# oscilostor.net
KiCad netlist of a schematic drawn in Altium Designer
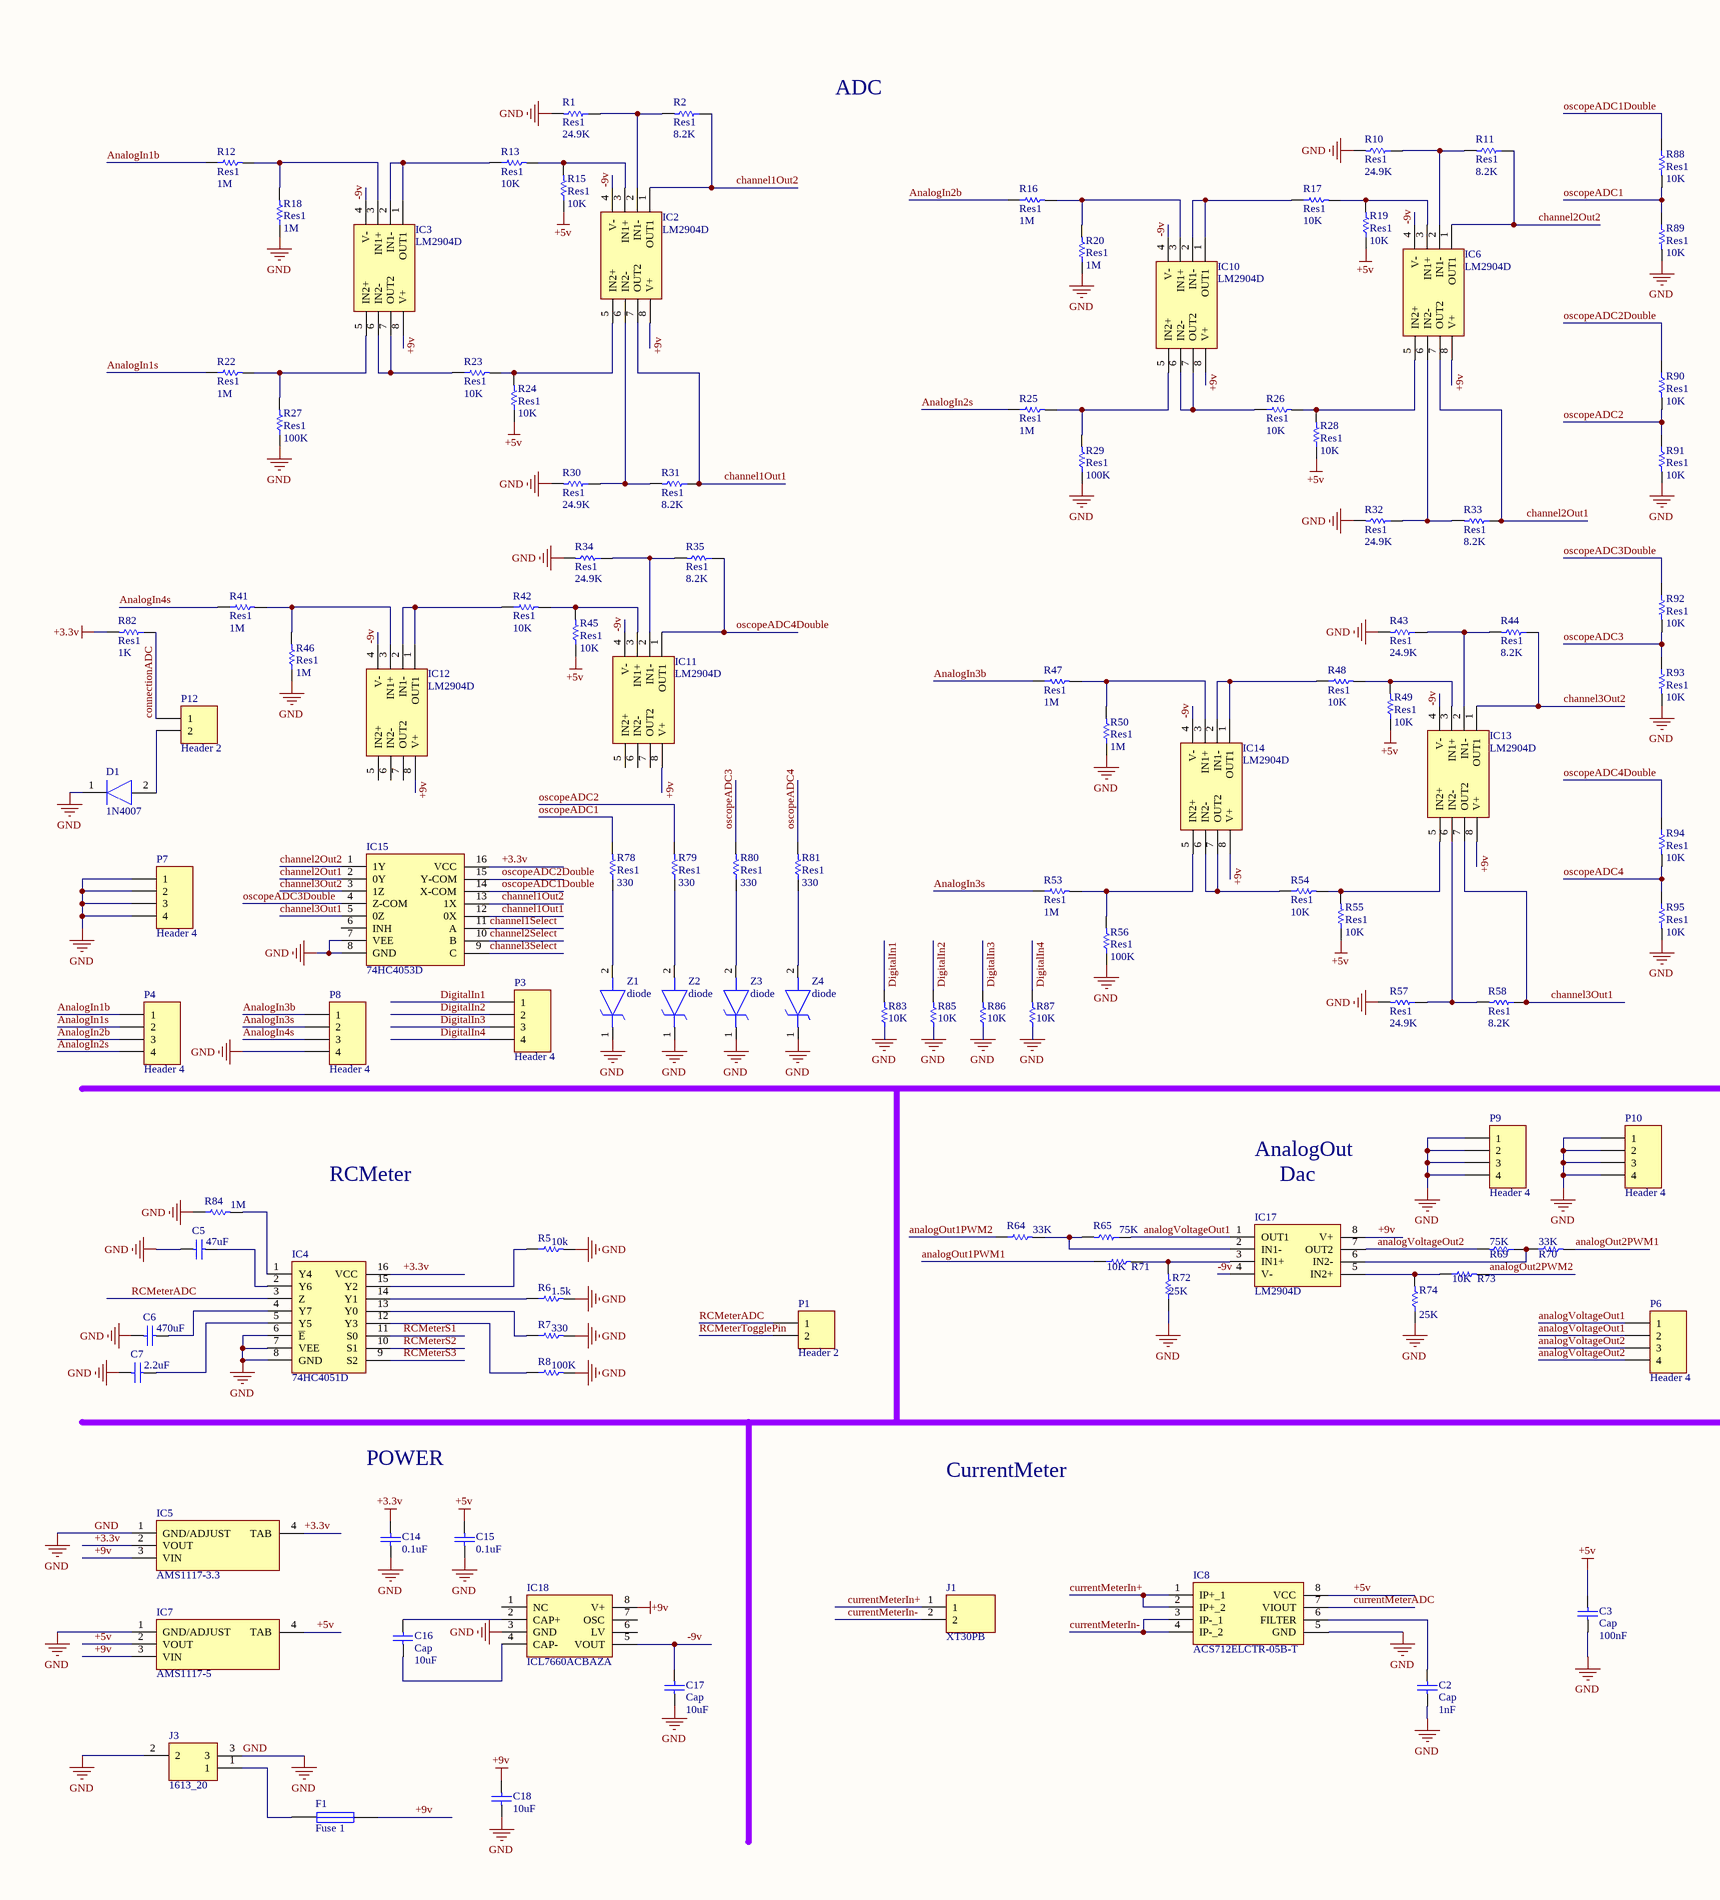
[diagram p0: oscilostor.SchDoc, left]
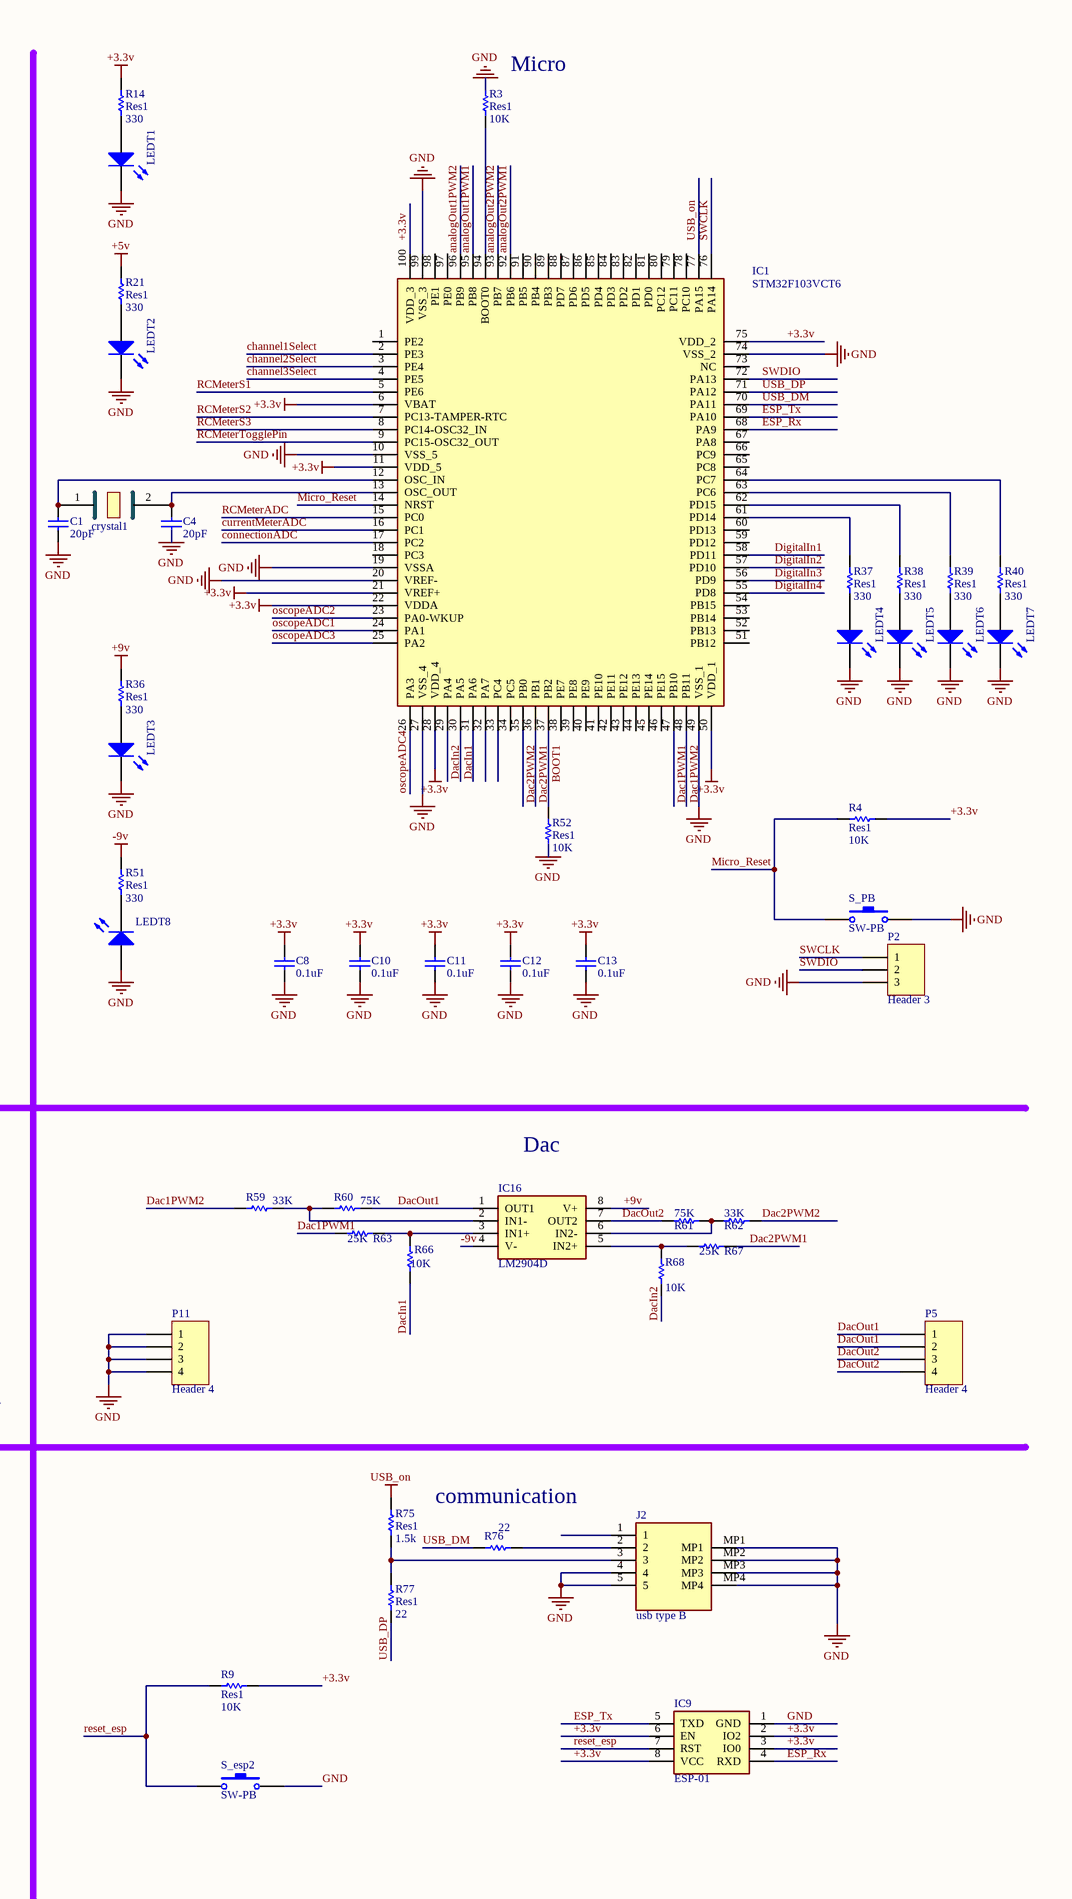
[diagram p1: oscilostor.SchDoc, right]

(export (version "E")
  (design (tool "Eeschema 10.0.6"))
  (components
    (comp (ref "C1")
      (value "20pF")
      (footprint "J1-0603")
      (description "Ceramic Chip Capacitor - Standard")
      (fields (field (name "Comment") "C0603") (field (name "PUBLISHER") "Altium Limited"))
      (libsource (lib "KEMET Chip Capacitor") (part "C0603"))
    )
    (comp (ref "C2")
      (value "Cap")
      (footprint "J1-0603")
      (description "Capacitor")
      (fields (field (name "ALTIUM_VALUE") "1nF") (field (name "PUBLISHER") "Altium Limited"))
      (libsource (lib "Miscellaneous Devices") (part "Cap"))
    )
    (comp (ref "C3")
      (value "Cap")
      (footprint "J1-0603")
      (description "Capacitor")
      (fields (field (name "ALTIUM_VALUE") "100nF") (field (name "PUBLISHER") "Altium Limited"))
      (libsource (lib "Miscellaneous Devices") (part "Cap"))
    )
    (comp (ref "C4")
      (value "20pF")
      (footprint "J1-0603")
      (description "Ceramic Chip Capacitor - Standard")
      (fields (field (name "Comment") "C0603") (field (name "PUBLISHER") "Altium Limited"))
      (libsource (lib "KEMET Chip Capacitor") (part "C0603"))
    )
    (comp (ref "C5")
      (value "47uF")
      (footprint "Deep Cap gerdaloo")
      (description "Capacitor")
      (fields (field (name "Comment") "Cap") (field (name "PUBLISHER") "Altium Limited"))
      (libsource (lib "Miscellaneous Devices") (part "Cap"))
    )
    (comp (ref "C6")
      (value "470uF")
      (footprint "Deep Cap gerdaloo")
      (description "Capacitor")
      (fields (field (name "Comment") "Cap") (field (name "PUBLISHER") "Altium Limited"))
      (libsource (lib "Miscellaneous Devices") (part "Cap"))
    )
    (comp (ref "C7")
      (value "2.2uF")
      (footprint "Deep Cap gerdaloo")
      (description "Capacitor")
      (fields (field (name "Comment") "Cap") (field (name "PUBLISHER") "Altium Limited"))
      (libsource (lib "Miscellaneous Devices") (part "Cap"))
    )
    (comp (ref "C8")
      (value "0.1uF")
      (footprint "J1-0603")
      (description "Ceramic Chip Capacitor - Standard")
      (fields (field (name "Comment") "C0603") (field (name "PUBLISHER") "Altium Limited"))
      (libsource (lib "KEMET Chip Capacitor") (part "C0603"))
    )
    (comp (ref "C10")
      (value "0.1uF")
      (footprint "J1-0603")
      (description "Ceramic Chip Capacitor - Standard")
      (fields (field (name "Comment") "C0603") (field (name "PUBLISHER") "Altium Limited"))
      (libsource (lib "KEMET Chip Capacitor") (part "C0603"))
    )
    (comp (ref "C11")
      (value "0.1uF")
      (footprint "J1-0603")
      (description "Ceramic Chip Capacitor - Standard")
      (fields (field (name "Comment") "C0603") (field (name "PUBLISHER") "Altium Limited"))
      (libsource (lib "KEMET Chip Capacitor") (part "C0603"))
    )
    (comp (ref "C12")
      (value "0.1uF")
      (footprint "J1-0603")
      (description "Ceramic Chip Capacitor - Standard")
      (fields (field (name "Comment") "C0603") (field (name "PUBLISHER") "Altium Limited"))
      (libsource (lib "KEMET Chip Capacitor") (part "C0603"))
    )
    (comp (ref "C13")
      (value "0.1uF")
      (footprint "J1-0603")
      (description "Ceramic Chip Capacitor - Standard")
      (fields (field (name "Comment") "C0603") (field (name "PUBLISHER") "Altium Limited"))
      (libsource (lib "KEMET Chip Capacitor") (part "C0603"))
    )
    (comp (ref "C14")
      (value "0.1uF")
      (footprint "J1-0603")
      (description "Ceramic Chip Capacitor - Standard")
      (fields (field (name "Comment") "C0603") (field (name "PUBLISHER") "Altium Limited"))
      (libsource (lib "KEMET Chip Capacitor") (part "C0603"))
    )
    (comp (ref "C15")
      (value "0.1uF")
      (footprint "J1-0603")
      (description "Ceramic Chip Capacitor - Standard")
      (fields (field (name "Comment") "C0603") (field (name "PUBLISHER") "Altium Limited"))
      (libsource (lib "KEMET Chip Capacitor") (part "C0603"))
    )
    (comp (ref "C16")
      (value "Cap")
      (footprint "J1-0603")
      (description "Capacitor")
      (fields (field (name "ALTIUM_VALUE") "10uF") (field (name "PUBLISHER") "Altium Limited"))
      (libsource (lib "Miscellaneous Devices") (part "Cap"))
    )
    (comp (ref "C17")
      (value "Cap")
      (footprint "J1-0603")
      (description "Capacitor")
      (fields (field (name "ALTIUM_VALUE") "10uF") (field (name "PUBLISHER") "Altium Limited"))
      (libsource (lib "Miscellaneous Devices") (part "Cap"))
    )
    (comp (ref "C18")
      (value "10uF")
      (footprint "J1-0603")
      (description "Ceramic Chip Capacitor - Standard")
      (fields (field (name "Comment") "C0603") (field (name "PUBLISHER") "Altium Limited"))
      (libsource (lib "KEMET Chip Capacitor") (part "C0603"))
    )
    (comp (ref "crystal1")
      (value "clockProducerDeep")
      (footprint "smd CRYSTAL")
      (libsource (lib "Schlib1") (part "deep crystal"))
    )
    (comp (ref "D1")
      (value "1N4007")
      (footprint "SamacSys:DIOM5327X242N")
      (description "Diode")
      (libsource (lib "*") (part "1N4007"))
    )
    (comp (ref "F1")
      (value "Fuse 1")
      (footprint "0805")
      (description "Fuse")
      (fields (field (name "PUBLISHER") "Altium Limited"))
      (libsource (lib "Miscellaneous Devices") (part "Fuse 1"))
    )
    (comp (ref "IC1")
      (value "STM32F103VCT6")
      (footprint "SamacSys:QFP50P1600X1600X160-100N")
      (description "Integrated Circuit")
      (fields (field (name "MOUSER PART NUMBER") "511-STM32F103VCT6"))
      (libsource (lib "*") (part "STM32F103VCT6"))
    )
    (comp (ref "IC2")
      (value "LM2904D")
      (footprint "SamacSys:SOIC127P600X175-8N")
      (description "Integrated Circuit")
      (fields (field (name "MOUSER PART NUMBER") "595-LM2904D"))
      (libsource (lib "*") (part "LM2904D"))
    )
    (comp (ref "IC3")
      (value "LM2904D")
      (footprint "SamacSys:SOIC127P600X175-8N")
      (description "Integrated Circuit")
      (fields (field (name "MOUSER PART NUMBER") "595-LM2904D"))
      (libsource (lib "*") (part "LM2904D"))
    )
    (comp (ref "IC4")
      (value "74HC4051D")
      (footprint "SamacSys:SOIC127P600X175-16N")
      (description "Integrated Circuit")
      (libsource (lib "*") (part "74HC4051D"))
    )
    (comp (ref "IC5")
      (value "AMS1117-3.3")
      (footprint "SamacSys:SOT229P700X180-4N")
      (description "Integrated Circuit")
      (fields (field (name "MANUFACTURER_PART_NUMBER") "AMS1117-1.5"))
      (libsource (lib "*") (part "AMS1117-1.5"))
    )
    (comp (ref "IC6")
      (value "LM2904D")
      (footprint "SamacSys:SOIC127P600X175-8N")
      (description "Integrated Circuit")
      (fields (field (name "MOUSER PART NUMBER") "595-LM2904D"))
      (libsource (lib "*") (part "LM2904D"))
    )
    (comp (ref "IC7")
      (value "AMS1117-5")
      (footprint "SamacSys:SOT229P700X180-4N")
      (description "Integrated Circuit")
      (fields (field (name "MANUFACTURER_PART_NUMBER") "AMS1117-1.5"))
      (libsource (lib "*") (part "AMS1117-1.5"))
    )
    (comp (ref "IC8")
      (value "ACS712ELCTR-05B-T")
      (footprint "SamacSys:SOIC127P600X175-8N")
      (description "Integrated Circuit")
      (libsource (lib "*") (part "ACS712ELCTR-05B-T"))
    )
    (comp (ref "IC9")
      (value "ESP-01")
      (footprint "HDR2X4")
      (description "Integrated Circuit")
      (libsource (lib "*") (part "ESP-01"))
    )
    (comp (ref "IC10")
      (value "LM2904D")
      (footprint "SamacSys:SOIC127P600X175-8N")
      (description "Integrated Circuit")
      (fields (field (name "MOUSER PART NUMBER") "595-LM2904D"))
      (libsource (lib "*") (part "LM2904D"))
    )
    (comp (ref "IC11")
      (value "LM2904D")
      (footprint "SamacSys:SOIC127P600X175-8N")
      (description "Integrated Circuit")
      (fields (field (name "MOUSER PART NUMBER") "595-LM2904D"))
      (libsource (lib "*") (part "LM2904D"))
    )
    (comp (ref "IC12")
      (value "LM2904D")
      (footprint "SamacSys:SOIC127P600X175-8N")
      (description "Integrated Circuit")
      (fields (field (name "MOUSER PART NUMBER") "595-LM2904D"))
      (libsource (lib "*") (part "LM2904D"))
    )
    (comp (ref "IC13")
      (value "LM2904D")
      (footprint "SamacSys:SOIC127P600X175-8N")
      (description "Integrated Circuit")
      (fields (field (name "MOUSER PART NUMBER") "595-LM2904D"))
      (libsource (lib "*") (part "LM2904D"))
    )
    (comp (ref "IC14")
      (value "LM2904D")
      (footprint "SamacSys:SOIC127P600X175-8N")
      (description "Integrated Circuit")
      (fields (field (name "MOUSER PART NUMBER") "595-LM2904D"))
      (libsource (lib "*") (part "LM2904D"))
    )
    (comp (ref "IC15")
      (value "74HC4053D")
      (footprint "SamacSys:SOIC127P600X175-16N")
      (description "Integrated Circuit")
      (fields (field (name "MOUSER PART NUMBER") "757-74HC4053D"))
      (libsource (lib "*") (part "74HC4053D"))
    )
    (comp (ref "IC16")
      (value "LM2904D")
      (footprint "SamacSys:SOIC127P600X175-8N")
      (description "Integrated Circuit")
      (fields (field (name "MOUSER PART NUMBER") "595-LM2904D"))
      (libsource (lib "") (part "LM2904D_1"))
    )
    (comp (ref "IC17")
      (value "LM2904D")
      (footprint "SamacSys:SOIC127P600X175-8N")
      (description "Integrated Circuit")
      (fields (field (name "MOUSER PART NUMBER") "595-LM2904D"))
      (libsource (lib "") (part "LM2904D_1"))
    )
    (comp (ref "IC18")
      (value "ICL7660ACBAZA")
      (footprint "SamacSys:SOIC127P600X175-8N")
      (description "Integrated Circuit")
      (fields (field (name "MOUSER PART NUMBER") "968-ICL7660ACBAZA"))
      (libsource (lib "*") (part "ICL7660ACBAZA"))
    )
    (comp (ref "J1")
      (value "XT30PB")
      (footprint "SamacSys:XT30PB")
      (description "Connector")
      (libsource (lib "*") (part "XT30PB"))
    )
    (comp (ref "J2")
      (value "usb type B")
      (footprint "SamacSys:0474910001")
      (description "Connector")
      (fields (field (name "MANUFACTURER_PART_NUMBER") "0474910001"))
      (libsource (lib "SamacSys") (part "0474910001"))
    )
    (comp (ref "J3")
      (value "1613_20")
      (footprint "SamacSys:161320")
      (description "Connector")
      (fields (field (name "MANUFACTURER_PART_NUMBER") "1613 20"))
      (libsource (lib "*") (part "1613_20"))
    )
    (comp (ref "LEDT1")
      (value "~")
      (footprint "3518")
      (description "Typical BLUE SiC LED")
      (fields (field (name "PUBLISHER") "Altium Limited"))
      (libsource (lib "Miscellaneous Devices") (part "LED3"))
    )
    (comp (ref "LEDT2")
      (value "~")
      (footprint "3518")
      (description "Typical BLUE SiC LED")
      (fields (field (name "PUBLISHER") "Altium Limited"))
      (libsource (lib "Miscellaneous Devices") (part "LED3"))
    )
    (comp (ref "LEDT3")
      (value "~")
      (footprint "3518")
      (description "Typical BLUE SiC LED")
      (fields (field (name "PUBLISHER") "Altium Limited"))
      (libsource (lib "Miscellaneous Devices") (part "LED3"))
    )
    (comp (ref "LEDT4")
      (value "~")
      (footprint "3518")
      (description "Typical BLUE SiC LED")
      (fields (field (name "PUBLISHER") "Altium Limited"))
      (libsource (lib "Miscellaneous Devices") (part "LED3"))
    )
    (comp (ref "LEDT5")
      (value "~")
      (footprint "3518")
      (description "Typical BLUE SiC LED")
      (fields (field (name "PUBLISHER") "Altium Limited"))
      (libsource (lib "Miscellaneous Devices") (part "LED3"))
    )
    (comp (ref "LEDT6")
      (value "~")
      (footprint "3518")
      (description "Typical BLUE SiC LED")
      (fields (field (name "PUBLISHER") "Altium Limited"))
      (libsource (lib "Miscellaneous Devices") (part "LED3"))
    )
    (comp (ref "LEDT7")
      (value "~")
      (footprint "3518")
      (description "Typical BLUE SiC LED")
      (fields (field (name "PUBLISHER") "Altium Limited"))
      (libsource (lib "Miscellaneous Devices") (part "LED3"))
    )
    (comp (ref "LEDT8")
      (value "~")
      (footprint "3518")
      (description "Typical BLUE SiC LED")
      (fields (field (name "PUBLISHER") "Altium Limited"))
      (libsource (lib "Miscellaneous Devices") (part "LED3"))
    )
    (comp (ref "P1")
      (value "Header 2")
      (footprint "HDR1X2")
      (description "Header, 2-Pin")
      (fields (field (name "PUBLISHER") "Altium Limited"))
      (libsource (lib "Miscellaneous Connectors") (part "Header 2"))
    )
    (comp (ref "P2")
      (value "Header 3")
      (footprint "HDR1X3")
      (description "Header, 3-Pin")
      (fields (field (name "PUBLISHER") "Altium Limited"))
      (libsource (lib "Miscellaneous Connectors") (part "Header 3"))
    )
    (comp (ref "P3")
      (value "Header 4")
      (footprint "HDR1X4")
      (description "Header, 4-Pin")
      (fields (field (name "PUBLISHER") "Altium Limited"))
      (libsource (lib "Miscellaneous Connectors") (part "Header 4"))
    )
    (comp (ref "P4")
      (value "Header 4")
      (footprint "HDR1X4")
      (description "Header, 4-Pin")
      (fields (field (name "PUBLISHER") "Altium Limited"))
      (libsource (lib "Miscellaneous Connectors") (part "Header 4"))
    )
    (comp (ref "P5")
      (value "Header 4")
      (footprint "HDR1X4")
      (description "Header, 4-Pin")
      (fields (field (name "PUBLISHER") "Altium Limited"))
      (libsource (lib "Miscellaneous Connectors") (part "Header 4"))
    )
    (comp (ref "P6")
      (value "Header 4")
      (footprint "HDR1X4")
      (description "Header, 4-Pin")
      (fields (field (name "PUBLISHER") "Altium Limited"))
      (libsource (lib "Miscellaneous Connectors") (part "Header 4"))
    )
    (comp (ref "P7")
      (value "Header 4")
      (footprint "HDR1X4")
      (description "Header, 4-Pin")
      (fields (field (name "PUBLISHER") "Altium Limited"))
      (libsource (lib "Miscellaneous Connectors") (part "Header 4"))
    )
    (comp (ref "P8")
      (value "Header 4")
      (footprint "HDR1X4")
      (description "Header, 4-Pin")
      (fields (field (name "PUBLISHER") "Altium Limited"))
      (libsource (lib "Miscellaneous Connectors") (part "Header 4"))
    )
    (comp (ref "P9")
      (value "Header 4")
      (footprint "HDR1X4")
      (description "Header, 4-Pin")
      (fields (field (name "PUBLISHER") "Altium Limited"))
      (libsource (lib "Miscellaneous Connectors") (part "Header 4"))
    )
    (comp (ref "P10")
      (value "Header 4")
      (footprint "HDR1X4")
      (description "Header, 4-Pin")
      (fields (field (name "PUBLISHER") "Altium Limited"))
      (libsource (lib "Miscellaneous Connectors") (part "Header 4"))
    )
    (comp (ref "P11")
      (value "Header 4")
      (footprint "HDR1X4")
      (description "Header, 4-Pin")
      (fields (field (name "PUBLISHER") "Altium Limited"))
      (libsource (lib "Miscellaneous Connectors") (part "Header 4"))
    )
    (comp (ref "P12")
      (value "Header 2")
      (footprint "HDR1X2")
      (description "Header, 2-Pin")
      (fields (field (name "PUBLISHER") "Altium Limited"))
      (libsource (lib "Miscellaneous Connectors") (part "Header 2"))
    )
    (comp (ref "R1")
      (value "Res1")
      (footprint "J1-0603")
      (description "Resistor")
      (fields (field (name "ALTIUM_VALUE") "24.9K") (field (name "PUBLISHER") "Altium Limited"))
      (libsource (lib "Miscellaneous Devices") (part "Res1"))
    )
    (comp (ref "R2")
      (value "Res1")
      (footprint "J1-0603")
      (description "Resistor")
      (fields (field (name "ALTIUM_VALUE") "8.2K") (field (name "PUBLISHER") "Altium Limited"))
      (libsource (lib "Miscellaneous Devices") (part "Res1"))
    )
    (comp (ref "R3")
      (value "Res1")
      (footprint "J1-0603")
      (description "Resistor")
      (fields (field (name "ALTIUM_VALUE") "10K") (field (name "PUBLISHER") "Altium Limited"))
      (libsource (lib "Miscellaneous Devices") (part "Res1"))
    )
    (comp (ref "R4")
      (value "Res1")
      (footprint "J1-0603")
      (description "Resistor")
      (fields (field (name "ALTIUM_VALUE") "10K") (field (name "PUBLISHER") "Altium Limited"))
      (libsource (lib "Miscellaneous Devices") (part "Res1"))
    )
    (comp (ref "R5")
      (value "10k")
      (footprint "J1-0603")
      (description "Resistor")
      (fields (field (name "Comment") "Res1") (field (name "PUBLISHER") "Altium Limited"))
      (libsource (lib "Miscellaneous Devices") (part "Res1"))
    )
    (comp (ref "R6")
      (value "1.5k")
      (footprint "J1-0603")
      (description "Resistor")
      (fields (field (name "Comment") "Res1") (field (name "PUBLISHER") "Altium Limited"))
      (libsource (lib "Miscellaneous Devices") (part "Res1"))
    )
    (comp (ref "R7")
      (value "330")
      (footprint "J1-0603")
      (description "Resistor")
      (fields (field (name "Comment") "Res1") (field (name "PUBLISHER") "Altium Limited"))
      (libsource (lib "Miscellaneous Devices") (part "Res1"))
    )
    (comp (ref "R8")
      (value "100K")
      (footprint "J1-0603")
      (description "Resistor")
      (fields (field (name "Comment") "Res1") (field (name "PUBLISHER") "Altium Limited"))
      (libsource (lib "Miscellaneous Devices") (part "Res1"))
    )
    (comp (ref "R9")
      (value "Res1")
      (footprint "J1-0603")
      (description "Resistor")
      (fields (field (name "ALTIUM_VALUE") "10K") (field (name "PUBLISHER") "Altium Limited"))
      (libsource (lib "Miscellaneous Devices") (part "Res1"))
    )
    (comp (ref "R10")
      (value "Res1")
      (footprint "J1-0603")
      (description "Resistor")
      (fields (field (name "ALTIUM_VALUE") "24.9K") (field (name "PUBLISHER") "Altium Limited"))
      (libsource (lib "Miscellaneous Devices") (part "Res1"))
    )
    (comp (ref "R11")
      (value "Res1")
      (footprint "J1-0603")
      (description "Resistor")
      (fields (field (name "ALTIUM_VALUE") "8.2K") (field (name "PUBLISHER") "Altium Limited"))
      (libsource (lib "Miscellaneous Devices") (part "Res1"))
    )
    (comp (ref "R12")
      (value "Res1")
      (footprint "J1-0603")
      (description "Resistor")
      (fields (field (name "ALTIUM_VALUE") "1M") (field (name "PUBLISHER") "Altium Limited"))
      (libsource (lib "Miscellaneous Devices") (part "Res1"))
    )
    (comp (ref "R13")
      (value "Res1")
      (footprint "J1-0603")
      (description "Resistor")
      (fields (field (name "ALTIUM_VALUE") "10K") (field (name "PUBLISHER") "Altium Limited"))
      (libsource (lib "Miscellaneous Devices") (part "Res1"))
    )
    (comp (ref "R14")
      (value "Res1")
      (footprint "j1-0603")
      (description "Resistor")
      (fields (field (name "ALTIUM_VALUE") "330") (field (name "PUBLISHER") "Altium Limited"))
      (libsource (lib "Miscellaneous Devices") (part "Res1"))
    )
    (comp (ref "R15")
      (value "Res1")
      (footprint "J1-0603")
      (description "Resistor")
      (fields (field (name "ALTIUM_VALUE") "10K") (field (name "PUBLISHER") "Altium Limited"))
      (libsource (lib "Miscellaneous Devices") (part "Res1"))
    )
    (comp (ref "R16")
      (value "Res1")
      (footprint "J1-0603")
      (description "Resistor")
      (fields (field (name "ALTIUM_VALUE") "1M") (field (name "PUBLISHER") "Altium Limited"))
      (libsource (lib "Miscellaneous Devices") (part "Res1"))
    )
    (comp (ref "R17")
      (value "Res1")
      (footprint "J1-0603")
      (description "Resistor")
      (fields (field (name "ALTIUM_VALUE") "10K") (field (name "PUBLISHER") "Altium Limited"))
      (libsource (lib "Miscellaneous Devices") (part "Res1"))
    )
    (comp (ref "R18")
      (value "Res1")
      (footprint "J1-0603")
      (description "Resistor")
      (fields (field (name "ALTIUM_VALUE") "1M") (field (name "PUBLISHER") "Altium Limited"))
      (libsource (lib "Miscellaneous Devices") (part "Res1"))
    )
    (comp (ref "R19")
      (value "Res1")
      (footprint "J1-0603")
      (description "Resistor")
      (fields (field (name "ALTIUM_VALUE") "10K") (field (name "PUBLISHER") "Altium Limited"))
      (libsource (lib "Miscellaneous Devices") (part "Res1"))
    )
    (comp (ref "R20")
      (value "Res1")
      (footprint "J1-0603")
      (description "Resistor")
      (fields (field (name "ALTIUM_VALUE") "1M") (field (name "PUBLISHER") "Altium Limited"))
      (libsource (lib "Miscellaneous Devices") (part "Res1"))
    )
    (comp (ref "R21")
      (value "Res1")
      (footprint "j1-0603")
      (description "Resistor")
      (fields (field (name "ALTIUM_VALUE") "330") (field (name "PUBLISHER") "Altium Limited"))
      (libsource (lib "Miscellaneous Devices") (part "Res1"))
    )
    (comp (ref "R22")
      (value "Res1")
      (footprint "J1-0603")
      (description "Resistor")
      (fields (field (name "ALTIUM_VALUE") "1M") (field (name "PUBLISHER") "Altium Limited"))
      (libsource (lib "Miscellaneous Devices") (part "Res1"))
    )
    (comp (ref "R23")
      (value "Res1")
      (footprint "J1-0603")
      (description "Resistor")
      (fields (field (name "ALTIUM_VALUE") "10K") (field (name "PUBLISHER") "Altium Limited"))
      (libsource (lib "Miscellaneous Devices") (part "Res1"))
    )
    (comp (ref "R24")
      (value "Res1")
      (footprint "J1-0603")
      (description "Resistor")
      (fields (field (name "ALTIUM_VALUE") "10K") (field (name "PUBLISHER") "Altium Limited"))
      (libsource (lib "Miscellaneous Devices") (part "Res1"))
    )
    (comp (ref "R25")
      (value "Res1")
      (footprint "J1-0603")
      (description "Resistor")
      (fields (field (name "ALTIUM_VALUE") "1M") (field (name "PUBLISHER") "Altium Limited"))
      (libsource (lib "Miscellaneous Devices") (part "Res1"))
    )
    (comp (ref "R26")
      (value "Res1")
      (footprint "J1-0603")
      (description "Resistor")
      (fields (field (name "ALTIUM_VALUE") "10K") (field (name "PUBLISHER") "Altium Limited"))
      (libsource (lib "Miscellaneous Devices") (part "Res1"))
    )
    (comp (ref "R27")
      (value "Res1")
      (footprint "J1-0603")
      (description "Resistor")
      (fields (field (name "ALTIUM_VALUE") "100K") (field (name "PUBLISHER") "Altium Limited"))
      (libsource (lib "Miscellaneous Devices") (part "Res1"))
    )
    (comp (ref "R28")
      (value "Res1")
      (footprint "J1-0603")
      (description "Resistor")
      (fields (field (name "ALTIUM_VALUE") "10K") (field (name "PUBLISHER") "Altium Limited"))
      (libsource (lib "Miscellaneous Devices") (part "Res1"))
    )
    (comp (ref "R29")
      (value "Res1")
      (footprint "J1-0603")
      (description "Resistor")
      (fields (field (name "ALTIUM_VALUE") "100K") (field (name "PUBLISHER") "Altium Limited"))
      (libsource (lib "Miscellaneous Devices") (part "Res1"))
    )
    (comp (ref "R30")
      (value "Res1")
      (footprint "J1-0603")
      (description "Resistor")
      (fields (field (name "ALTIUM_VALUE") "24.9K") (field (name "PUBLISHER") "Altium Limited"))
      (libsource (lib "Miscellaneous Devices") (part "Res1"))
    )
    (comp (ref "R31")
      (value "Res1")
      (footprint "J1-0603")
      (description "Resistor")
      (fields (field (name "ALTIUM_VALUE") "8.2K") (field (name "PUBLISHER") "Altium Limited"))
      (libsource (lib "Miscellaneous Devices") (part "Res1"))
    )
    (comp (ref "R32")
      (value "Res1")
      (footprint "J1-0603")
      (description "Resistor")
      (fields (field (name "ALTIUM_VALUE") "24.9K") (field (name "PUBLISHER") "Altium Limited"))
      (libsource (lib "Miscellaneous Devices") (part "Res1"))
    )
    (comp (ref "R33")
      (value "Res1")
      (footprint "J1-0603")
      (description "Resistor")
      (fields (field (name "ALTIUM_VALUE") "8.2K") (field (name "PUBLISHER") "Altium Limited"))
      (libsource (lib "Miscellaneous Devices") (part "Res1"))
    )
    (comp (ref "R34")
      (value "Res1")
      (footprint "J1-0603")
      (description "Resistor")
      (fields (field (name "ALTIUM_VALUE") "24.9K") (field (name "PUBLISHER") "Altium Limited"))
      (libsource (lib "Miscellaneous Devices") (part "Res1"))
    )
    (comp (ref "R35")
      (value "Res1")
      (footprint "J1-0603")
      (description "Resistor")
      (fields (field (name "ALTIUM_VALUE") "8.2K") (field (name "PUBLISHER") "Altium Limited"))
      (libsource (lib "Miscellaneous Devices") (part "Res1"))
    )
    (comp (ref "R36")
      (value "Res1")
      (footprint "j1-0603")
      (description "Resistor")
      (fields (field (name "ALTIUM_VALUE") "330") (field (name "PUBLISHER") "Altium Limited"))
      (libsource (lib "Miscellaneous Devices") (part "Res1"))
    )
    (comp (ref "R37")
      (value "Res1")
      (footprint "j1-0603")
      (description "Resistor")
      (fields (field (name "ALTIUM_VALUE") "330") (field (name "PUBLISHER") "Altium Limited"))
      (libsource (lib "Miscellaneous Devices") (part "Res1"))
    )
    (comp (ref "R38")
      (value "Res1")
      (footprint "j1-0603")
      (description "Resistor")
      (fields (field (name "ALTIUM_VALUE") "330") (field (name "PUBLISHER") "Altium Limited"))
      (libsource (lib "Miscellaneous Devices") (part "Res1"))
    )
    (comp (ref "R39")
      (value "Res1")
      (footprint "j1-0603")
      (description "Resistor")
      (fields (field (name "ALTIUM_VALUE") "330") (field (name "PUBLISHER") "Altium Limited"))
      (libsource (lib "Miscellaneous Devices") (part "Res1"))
    )
    (comp (ref "R40")
      (value "Res1")
      (footprint "j1-0603")
      (description "Resistor")
      (fields (field (name "ALTIUM_VALUE") "330") (field (name "PUBLISHER") "Altium Limited"))
      (libsource (lib "Miscellaneous Devices") (part "Res1"))
    )
    (comp (ref "R41")
      (value "Res1")
      (footprint "J1-0603")
      (description "Resistor")
      (fields (field (name "ALTIUM_VALUE") "1M") (field (name "PUBLISHER") "Altium Limited"))
      (libsource (lib "Miscellaneous Devices") (part "Res1"))
    )
    (comp (ref "R42")
      (value "Res1")
      (footprint "J1-0603")
      (description "Resistor")
      (fields (field (name "ALTIUM_VALUE") "10K") (field (name "PUBLISHER") "Altium Limited"))
      (libsource (lib "Miscellaneous Devices") (part "Res1"))
    )
    (comp (ref "R43")
      (value "Res1")
      (footprint "J1-0603")
      (description "Resistor")
      (fields (field (name "ALTIUM_VALUE") "24.9K") (field (name "PUBLISHER") "Altium Limited"))
      (libsource (lib "Miscellaneous Devices") (part "Res1"))
    )
    (comp (ref "R44")
      (value "Res1")
      (footprint "J1-0603")
      (description "Resistor")
      (fields (field (name "ALTIUM_VALUE") "8.2K") (field (name "PUBLISHER") "Altium Limited"))
      (libsource (lib "Miscellaneous Devices") (part "Res1"))
    )
    (comp (ref "R45")
      (value "Res1")
      (footprint "J1-0603")
      (description "Resistor")
      (fields (field (name "ALTIUM_VALUE") "10K") (field (name "PUBLISHER") "Altium Limited"))
      (libsource (lib "Miscellaneous Devices") (part "Res1"))
    )
    (comp (ref "R46")
      (value "Res1")
      (footprint "J1-0603")
      (description "Resistor")
      (fields (field (name "ALTIUM_VALUE") "1M") (field (name "PUBLISHER") "Altium Limited"))
      (libsource (lib "Miscellaneous Devices") (part "Res1"))
    )
    (comp (ref "R47")
      (value "Res1")
      (footprint "J1-0603")
      (description "Resistor")
      (fields (field (name "ALTIUM_VALUE") "1M") (field (name "PUBLISHER") "Altium Limited"))
      (libsource (lib "Miscellaneous Devices") (part "Res1"))
    )
    (comp (ref "R48")
      (value "Res1")
      (footprint "J1-0603")
      (description "Resistor")
      (fields (field (name "ALTIUM_VALUE") "10K") (field (name "PUBLISHER") "Altium Limited"))
      (libsource (lib "Miscellaneous Devices") (part "Res1"))
    )
    (comp (ref "R49")
      (value "Res1")
      (footprint "J1-0603")
      (description "Resistor")
      (fields (field (name "ALTIUM_VALUE") "10K") (field (name "PUBLISHER") "Altium Limited"))
      (libsource (lib "Miscellaneous Devices") (part "Res1"))
    )
    (comp (ref "R50")
      (value "Res1")
      (footprint "J1-0603")
      (description "Resistor")
      (fields (field (name "ALTIUM_VALUE") "1M") (field (name "PUBLISHER") "Altium Limited"))
      (libsource (lib "Miscellaneous Devices") (part "Res1"))
    )
    (comp (ref "R51")
      (value "Res1")
      (footprint "j1-0603")
      (description "Resistor")
      (fields (field (name "ALTIUM_VALUE") "330") (field (name "PUBLISHER") "Altium Limited"))
      (libsource (lib "Miscellaneous Devices") (part "Res1"))
    )
    (comp (ref "R52")
      (value "Res1")
      (footprint "J1-0603")
      (description "Resistor")
      (fields (field (name "ALTIUM_VALUE") "10K") (field (name "PUBLISHER") "Altium Limited"))
      (libsource (lib "Miscellaneous Devices") (part "Res1"))
    )
    (comp (ref "R53")
      (value "Res1")
      (footprint "J1-0603")
      (description "Resistor")
      (fields (field (name "ALTIUM_VALUE") "1M") (field (name "PUBLISHER") "Altium Limited"))
      (libsource (lib "Miscellaneous Devices") (part "Res1"))
    )
    (comp (ref "R54")
      (value "Res1")
      (footprint "J1-0603")
      (description "Resistor")
      (fields (field (name "ALTIUM_VALUE") "10K") (field (name "PUBLISHER") "Altium Limited"))
      (libsource (lib "Miscellaneous Devices") (part "Res1"))
    )
    (comp (ref "R55")
      (value "Res1")
      (footprint "J1-0603")
      (description "Resistor")
      (fields (field (name "ALTIUM_VALUE") "10K") (field (name "PUBLISHER") "Altium Limited"))
      (libsource (lib "Miscellaneous Devices") (part "Res1"))
    )
    (comp (ref "R56")
      (value "Res1")
      (footprint "J1-0603")
      (description "Resistor")
      (fields (field (name "ALTIUM_VALUE") "100K") (field (name "PUBLISHER") "Altium Limited"))
      (libsource (lib "Miscellaneous Devices") (part "Res1"))
    )
    (comp (ref "R57")
      (value "Res1")
      (footprint "J1-0603")
      (description "Resistor")
      (fields (field (name "ALTIUM_VALUE") "24.9K") (field (name "PUBLISHER") "Altium Limited"))
      (libsource (lib "Miscellaneous Devices") (part "Res1"))
    )
    (comp (ref "R58")
      (value "Res1")
      (footprint "J1-0603")
      (description "Resistor")
      (fields (field (name "ALTIUM_VALUE") "8.2K") (field (name "PUBLISHER") "Altium Limited"))
      (libsource (lib "Miscellaneous Devices") (part "Res1"))
    )
    (comp (ref "R59")
      (value "33K")
      (footprint "J1-0603")
      (description "Resistor")
      (fields (field (name "Comment") "Res1") (field (name "PUBLISHER") "Altium Limited"))
      (libsource (lib "Miscellaneous Devices") (part "Res1"))
    )
    (comp (ref "R60")
      (value "75K")
      (footprint "J1-0603")
      (description "Resistor")
      (fields (field (name "Comment") "Res1") (field (name "PUBLISHER") "Altium Limited"))
      (libsource (lib "Miscellaneous Devices") (part "Res1"))
    )
    (comp (ref "R61")
      (value "75K")
      (footprint "J1-0603")
      (description "Resistor")
      (fields (field (name "Comment") "Res1") (field (name "PUBLISHER") "Altium Limited"))
      (libsource (lib "Miscellaneous Devices") (part "Res1"))
    )
    (comp (ref "R62")
      (value "33K")
      (footprint "J1-0603")
      (description "Resistor")
      (fields (field (name "Comment") "Res1") (field (name "PUBLISHER") "Altium Limited"))
      (libsource (lib "Miscellaneous Devices") (part "Res1"))
    )
    (comp (ref "R63")
      (value "25K")
      (footprint "J1-0603")
      (description "Resistor")
      (fields (field (name "Comment") "Res1") (field (name "PUBLISHER") "Altium Limited"))
      (libsource (lib "Miscellaneous Devices") (part "Res1"))
    )
    (comp (ref "R64")
      (value "33K")
      (footprint "J1-0603")
      (description "Resistor")
      (fields (field (name "Comment") "Res1") (field (name "PUBLISHER") "Altium Limited"))
      (libsource (lib "Miscellaneous Devices") (part "Res1"))
    )
    (comp (ref "R65")
      (value "75K")
      (footprint "J1-0603")
      (description "Resistor")
      (fields (field (name "Comment") "Res1") (field (name "PUBLISHER") "Altium Limited"))
      (libsource (lib "Miscellaneous Devices") (part "Res1"))
    )
    (comp (ref "R66")
      (value "10K")
      (footprint "J1-0603")
      (description "Resistor")
      (fields (field (name "Comment") "Res1") (field (name "PUBLISHER") "Altium Limited"))
      (libsource (lib "Miscellaneous Devices") (part "Res1"))
    )
    (comp (ref "R67")
      (value "25K")
      (footprint "J1-0603")
      (description "Resistor")
      (fields (field (name "Comment") "Res1") (field (name "PUBLISHER") "Altium Limited"))
      (libsource (lib "Miscellaneous Devices") (part "Res1"))
    )
    (comp (ref "R68")
      (value "10K")
      (footprint "J1-0603")
      (description "Resistor")
      (fields (field (name "Comment") "Res1") (field (name "PUBLISHER") "Altium Limited"))
      (libsource (lib "Miscellaneous Devices") (part "Res1"))
    )
    (comp (ref "R69")
      (value "75K")
      (footprint "J1-0603")
      (description "Resistor")
      (fields (field (name "Comment") "Res1") (field (name "PUBLISHER") "Altium Limited"))
      (libsource (lib "Miscellaneous Devices") (part "Res1"))
    )
    (comp (ref "R70")
      (value "33K")
      (footprint "J1-0603")
      (description "Resistor")
      (fields (field (name "Comment") "Res1") (field (name "PUBLISHER") "Altium Limited"))
      (libsource (lib "Miscellaneous Devices") (part "Res1"))
    )
    (comp (ref "R71")
      (value "10K")
      (footprint "J1-0603")
      (description "Resistor")
      (fields (field (name "Comment") "Res1") (field (name "PUBLISHER") "Altium Limited"))
      (libsource (lib "Miscellaneous Devices") (part "Res1"))
    )
    (comp (ref "R72")
      (value "25K")
      (footprint "J1-0603")
      (description "Resistor")
      (fields (field (name "Comment") "Res1") (field (name "PUBLISHER") "Altium Limited"))
      (libsource (lib "Miscellaneous Devices") (part "Res1"))
    )
    (comp (ref "R73")
      (value "10K")
      (footprint "J1-0603")
      (description "Resistor")
      (fields (field (name "Comment") "Res1") (field (name "PUBLISHER") "Altium Limited"))
      (libsource (lib "Miscellaneous Devices") (part "Res1"))
    )
    (comp (ref "R74")
      (value "25K")
      (footprint "J1-0603")
      (description "Resistor")
      (fields (field (name "Comment") "Res1") (field (name "PUBLISHER") "Altium Limited"))
      (libsource (lib "Miscellaneous Devices") (part "Res1"))
    )
    (comp (ref "R75")
      (value "Res1")
      (footprint "J1-0603")
      (description "Resistor")
      (fields (field (name "ALTIUM_VALUE") "1.5k") (field (name "PUBLISHER") "Altium Limited"))
      (libsource (lib "Miscellaneous Devices") (part "Res1"))
    )
    (comp (ref "R76")
      (value "22")
      (footprint "J1-0603")
      (description "Resistor")
      (fields (field (name "Comment") "Res1") (field (name "PUBLISHER") "Altium Limited"))
      (libsource (lib "Miscellaneous Devices") (part "Res1"))
    )
    (comp (ref "R77")
      (value "Res1")
      (footprint "J1-0603")
      (description "Resistor")
      (fields (field (name "ALTIUM_VALUE") "22") (field (name "PUBLISHER") "Altium Limited"))
      (libsource (lib "Miscellaneous Devices") (part "Res1"))
    )
    (comp (ref "R78")
      (value "Res1")
      (footprint "J1-0603")
      (description "Resistor")
      (fields (field (name "ALTIUM_VALUE") "330") (field (name "PUBLISHER") "Altium Limited"))
      (libsource (lib "Miscellaneous Devices") (part "Res1"))
    )
    (comp (ref "R79")
      (value "Res1")
      (footprint "J1-0603")
      (description "Resistor")
      (fields (field (name "ALTIUM_VALUE") "330") (field (name "PUBLISHER") "Altium Limited"))
      (libsource (lib "Miscellaneous Devices") (part "Res1"))
    )
    (comp (ref "R80")
      (value "Res1")
      (footprint "J1-0603")
      (description "Resistor")
      (fields (field (name "ALTIUM_VALUE") "330") (field (name "PUBLISHER") "Altium Limited"))
      (libsource (lib "Miscellaneous Devices") (part "Res1"))
    )
    (comp (ref "R81")
      (value "Res1")
      (footprint "J1-0603")
      (description "Resistor")
      (fields (field (name "ALTIUM_VALUE") "330") (field (name "PUBLISHER") "Altium Limited"))
      (libsource (lib "Miscellaneous Devices") (part "Res1"))
    )
    (comp (ref "R82")
      (value "Res1")
      (footprint "J1-0603")
      (description "Resistor")
      (fields (field (name "ALTIUM_VALUE") "1K") (field (name "PUBLISHER") "Altium Limited"))
      (libsource (lib "Miscellaneous Devices") (part "Res1"))
    )
    (comp (ref "R83")
      (value "10K")
      (footprint "J1-0603")
      (description "Resistor")
      (fields (field (name "Comment") "Res1") (field (name "PUBLISHER") "Altium Limited"))
      (libsource (lib "Miscellaneous Devices") (part "Res1"))
    )
    (comp (ref "R84")
      (value "1M")
      (footprint "J1-0603")
      (description "Resistor")
      (fields (field (name "Comment") "Res1") (field (name "PUBLISHER") "Altium Limited"))
      (libsource (lib "Miscellaneous Devices") (part "Res1"))
    )
    (comp (ref "R85")
      (value "10K")
      (footprint "J1-0603")
      (description "Resistor")
      (fields (field (name "Comment") "Res1") (field (name "PUBLISHER") "Altium Limited"))
      (libsource (lib "Miscellaneous Devices") (part "Res1"))
    )
    (comp (ref "R86")
      (value "10K")
      (footprint "J1-0603")
      (description "Resistor")
      (fields (field (name "Comment") "Res1") (field (name "PUBLISHER") "Altium Limited"))
      (libsource (lib "Miscellaneous Devices") (part "Res1"))
    )
    (comp (ref "R87")
      (value "10K")
      (footprint "J1-0603")
      (description "Resistor")
      (fields (field (name "Comment") "Res1") (field (name "PUBLISHER") "Altium Limited"))
      (libsource (lib "Miscellaneous Devices") (part "Res1"))
    )
    (comp (ref "R88")
      (value "Res1")
      (footprint "J1-0603")
      (description "Resistor")
      (fields (field (name "ALTIUM_VALUE") "10K") (field (name "PUBLISHER") "Altium Limited"))
      (libsource (lib "Miscellaneous Devices") (part "Res1"))
    )
    (comp (ref "R89")
      (value "Res1")
      (footprint "J1-0603")
      (description "Resistor")
      (fields (field (name "ALTIUM_VALUE") "10K") (field (name "PUBLISHER") "Altium Limited"))
      (libsource (lib "Miscellaneous Devices") (part "Res1"))
    )
    (comp (ref "R90")
      (value "Res1")
      (footprint "J1-0603")
      (description "Resistor")
      (fields (field (name "ALTIUM_VALUE") "10K") (field (name "PUBLISHER") "Altium Limited"))
      (libsource (lib "Miscellaneous Devices") (part "Res1"))
    )
    (comp (ref "R91")
      (value "Res1")
      (footprint "J1-0603")
      (description "Resistor")
      (fields (field (name "ALTIUM_VALUE") "10K") (field (name "PUBLISHER") "Altium Limited"))
      (libsource (lib "Miscellaneous Devices") (part "Res1"))
    )
    (comp (ref "R92")
      (value "Res1")
      (footprint "J1-0603")
      (description "Resistor")
      (fields (field (name "ALTIUM_VALUE") "10K") (field (name "PUBLISHER") "Altium Limited"))
      (libsource (lib "Miscellaneous Devices") (part "Res1"))
    )
    (comp (ref "R93")
      (value "Res1")
      (footprint "J1-0603")
      (description "Resistor")
      (fields (field (name "ALTIUM_VALUE") "10K") (field (name "PUBLISHER") "Altium Limited"))
      (libsource (lib "Miscellaneous Devices") (part "Res1"))
    )
    (comp (ref "R94")
      (value "Res1")
      (footprint "J1-0603")
      (description "Resistor")
      (fields (field (name "ALTIUM_VALUE") "10K") (field (name "PUBLISHER") "Altium Limited"))
      (libsource (lib "Miscellaneous Devices") (part "Res1"))
    )
    (comp (ref "R95")
      (value "Res1")
      (footprint "J1-0603")
      (description "Resistor")
      (fields (field (name "ALTIUM_VALUE") "10K") (field (name "PUBLISHER") "Altium Limited"))
      (libsource (lib "Miscellaneous Devices") (part "Res1"))
    )
    (comp (ref "S_esp2")
      (value "SW-PB")
      (footprint "button")
      (description "Switch")
      (fields (field (name "PUBLISHER") "Altium Limited"))
      (libsource (lib "Miscellaneous Devices") (part "SW-PB"))
    )
    (comp (ref "S_PB")
      (value "SW-PB")
      (footprint "button")
      (description "Switch")
      (fields (field (name "PUBLISHER") "Altium Limited"))
      (libsource (lib "Miscellaneous Devices") (part "SW-PB"))
    )
    (comp (ref "Z1")
      (value "diode")
      (footprint "SamacSys:TZMC4V7GS08")
      (description "Zener Diode")
      (fields
        (field (name "MANUFACTURER_PART_NUMBER") "TZMC4V7-GS08")
        (field (name "MOUSER PART NUMBER") "78-TZMC4.7")
      )
      (libsource (lib "*") (part "TZMC4V7-GS08"))
    )
    (comp (ref "Z2")
      (value "diode")
      (footprint "SamacSys:TZMC4V7GS08")
      (description "Zener Diode")
      (fields
        (field (name "MANUFACTURER_PART_NUMBER") "TZMC4V7-GS08")
        (field (name "MOUSER PART NUMBER") "78-TZMC4.7")
      )
      (libsource (lib "*") (part "TZMC4V7-GS08"))
    )
    (comp (ref "Z3")
      (value "diode")
      (footprint "SamacSys:TZMC4V7GS08")
      (description "Zener Diode")
      (fields
        (field (name "MANUFACTURER_PART_NUMBER") "TZMC4V7-GS08")
        (field (name "MOUSER PART NUMBER") "78-TZMC4.7")
      )
      (libsource (lib "*") (part "TZMC4V7-GS08"))
    )
    (comp (ref "Z4")
      (value "diode")
      (footprint "SamacSys:TZMC4V7GS08")
      (description "Zener Diode")
      (fields
        (field (name "MANUFACTURER_PART_NUMBER") "TZMC4V7-GS08")
        (field (name "MOUSER PART NUMBER") "78-TZMC4.7")
      )
      (libsource (lib "*") (part "TZMC4V7-GS08"))
    )
  )
  (nets
    (net (code "1") (name "+3.3v") (class "Default")
      (node (ref "C10") (pin "1") (pinfunction "1_1") (pintype "passive"))
      (node (ref "C11") (pin "1") (pinfunction "1_1") (pintype "passive"))
      (node (ref "C12") (pin "1") (pinfunction "1_1") (pintype "passive"))
      (node (ref "C13") (pin "1") (pinfunction "1_1") (pintype "passive"))
      (node (ref "C14") (pin "1") (pinfunction "1_1") (pintype "passive"))
      (node (ref "C8") (pin "1") (pinfunction "1_1") (pintype "passive"))
      (node (ref "IC1") (pin "100") (pinfunction "VDD_3_100") (pintype "passive"))
      (node (ref "IC1") (pin "11") (pinfunction "VDD_5_11") (pintype "passive"))
      (node (ref "IC1") (pin "21") (pinfunction "VREF+_21") (pintype "passive"))
      (node (ref "IC1") (pin "22") (pinfunction "VDDA_22") (pintype "passive"))
      (node (ref "IC1") (pin "28") (pinfunction "VDD_4_28") (pintype "passive"))
      (node (ref "IC1") (pin "50") (pinfunction "VDD_1_50") (pintype "passive"))
      (node (ref "IC1") (pin "6") (pinfunction "VBAT_6") (pintype "passive"))
      (node (ref "IC1") (pin "75") (pinfunction "VDD_2_75") (pintype "passive"))
      (node (ref "IC15") (pin "16") (pinfunction "VCC_16") (pintype "passive"))
      (node (ref "IC4") (pin "16") (pinfunction "VCC_16") (pintype "passive"))
      (node (ref "IC5") (pin "2") (pinfunction "VOUT_2") (pintype "passive"))
      (node (ref "IC5") (pin "4") (pinfunction "TAB_4") (pintype "passive"))
      (node (ref "IC9") (pin "2") (pinfunction "IO2_2") (pintype "passive"))
      (node (ref "IC9") (pin "3") (pinfunction "IO0_3") (pintype "passive"))
      (node (ref "IC9") (pin "6") (pinfunction "EN_6") (pintype "passive"))
      (node (ref "IC9") (pin "8") (pinfunction "VCC_8") (pintype "passive"))
      (node (ref "R14") (pin "1") (pinfunction "1_1") (pintype "passive"))
      (node (ref "R4") (pin "2") (pinfunction "2_2") (pintype "passive"))
      (node (ref "R82") (pin "2") (pinfunction "2_2") (pintype "passive"))
      (node (ref "R9") (pin "2") (pinfunction "2_2") (pintype "passive"))
    )
    (net (code "2") (name "+5v") (class "Default")
      (node (ref "C15") (pin "1") (pinfunction "1_1") (pintype "passive"))
      (node (ref "C3") (pin "2") (pinfunction "2_2") (pintype "passive"))
      (node (ref "IC7") (pin "2") (pinfunction "VOUT_2") (pintype "passive"))
      (node (ref "IC7") (pin "4") (pinfunction "TAB_4") (pintype "passive"))
      (node (ref "IC8") (pin "8") (pinfunction "VCC_8") (pintype "passive"))
      (node (ref "R15") (pin "1") (pinfunction "1_1") (pintype "passive"))
      (node (ref "R19") (pin "1") (pinfunction "1_1") (pintype "passive"))
      (node (ref "R21") (pin "1") (pinfunction "1_1") (pintype "passive"))
      (node (ref "R24") (pin "1") (pinfunction "1_1") (pintype "passive"))
      (node (ref "R28") (pin "1") (pinfunction "1_1") (pintype "passive"))
      (node (ref "R45") (pin "1") (pinfunction "1_1") (pintype "passive"))
      (node (ref "R49") (pin "1") (pinfunction "1_1") (pintype "passive"))
      (node (ref "R55") (pin "1") (pinfunction "1_1") (pintype "passive"))
    )
    (net (code "3") (name "+9v") (class "Default")
      (node (ref "C18") (pin "1") (pinfunction "1_1") (pintype "passive"))
      (node (ref "F1") (pin "2") (pinfunction "2_2") (pintype "passive"))
      (node (ref "IC10") (pin "8") (pinfunction "V+_8") (pintype "passive"))
      (node (ref "IC11") (pin "8") (pinfunction "V+_8") (pintype "passive"))
      (node (ref "IC12") (pin "8") (pinfunction "V+_8") (pintype "passive"))
      (node (ref "IC13") (pin "8") (pinfunction "V+_8") (pintype "passive"))
      (node (ref "IC14") (pin "8") (pinfunction "V+_8") (pintype "passive"))
      (node (ref "IC16") (pin "8") (pinfunction "V+_8") (pintype "passive"))
      (node (ref "IC17") (pin "8") (pinfunction "V+_8") (pintype "passive"))
      (node (ref "IC18") (pin "8") (pinfunction "V+_8") (pintype "passive"))
      (node (ref "IC2") (pin "8") (pinfunction "V+_8") (pintype "passive"))
      (node (ref "IC3") (pin "8") (pinfunction "V+_8") (pintype "passive"))
      (node (ref "IC5") (pin "3") (pinfunction "VIN_3") (pintype "passive"))
      (node (ref "IC6") (pin "8") (pinfunction "V+_8") (pintype "passive"))
      (node (ref "IC7") (pin "3") (pinfunction "VIN_3") (pintype "passive"))
      (node (ref "R36") (pin "1") (pinfunction "1_1") (pintype "passive"))
    )
    (net (code "4") (name "-9v") (class "Default")
      (node (ref "C17") (pin "2") (pinfunction "2_2") (pintype "passive"))
      (node (ref "IC10") (pin "4") (pinfunction "V-_4") (pintype "passive"))
      (node (ref "IC11") (pin "4") (pinfunction "V-_4") (pintype "passive"))
      (node (ref "IC12") (pin "4") (pinfunction "V-_4") (pintype "passive"))
      (node (ref "IC13") (pin "4") (pinfunction "V-_4") (pintype "passive"))
      (node (ref "IC14") (pin "4") (pinfunction "V-_4") (pintype "passive"))
      (node (ref "IC16") (pin "4") (pinfunction "V-_4") (pintype "passive"))
      (node (ref "IC17") (pin "4") (pinfunction "V-_4") (pintype "passive"))
      (node (ref "IC18") (pin "5") (pinfunction "VOUT_5") (pintype "passive"))
      (node (ref "IC2") (pin "4") (pinfunction "V-_4") (pintype "passive"))
      (node (ref "IC3") (pin "4") (pinfunction "V-_4") (pintype "passive"))
      (node (ref "IC6") (pin "4") (pinfunction "V-_4") (pintype "passive"))
      (node (ref "R51") (pin "1") (pinfunction "1_1") (pintype "passive"))
    )
    (net (code "5") (name "/AnalogIn1b") (class "Default")
      (node (ref "P4") (pin "1") (pinfunction "1_1") (pintype "passive"))
      (node (ref "R12") (pin "1") (pinfunction "1_1") (pintype "passive"))
    )
    (net (code "6") (name "/AnalogIn1s") (class "Default")
      (node (ref "P4") (pin "2") (pinfunction "2_2") (pintype "passive"))
      (node (ref "R22") (pin "1") (pinfunction "1_1") (pintype "passive"))
    )
    (net (code "7") (name "/AnalogIn2b") (class "Default")
      (node (ref "P4") (pin "3") (pinfunction "3_3") (pintype "passive"))
      (node (ref "R16") (pin "1") (pinfunction "1_1") (pintype "passive"))
    )
    (net (code "8") (name "/AnalogIn2s") (class "Default")
      (node (ref "P4") (pin "4") (pinfunction "4_4") (pintype "passive"))
      (node (ref "R25") (pin "1") (pinfunction "1_1") (pintype "passive"))
    )
    (net (code "9") (name "/AnalogIn3b") (class "Default")
      (node (ref "P8") (pin "1") (pinfunction "1_1") (pintype "passive"))
      (node (ref "R47") (pin "1") (pinfunction "1_1") (pintype "passive"))
    )
    (net (code "10") (name "/AnalogIn3s") (class "Default")
      (node (ref "P8") (pin "2") (pinfunction "2_2") (pintype "passive"))
      (node (ref "R53") (pin "1") (pinfunction "1_1") (pintype "passive"))
    )
    (net (code "11") (name "/AnalogIn4s") (class "Default")
      (node (ref "P8") (pin "3") (pinfunction "3_3") (pintype "passive"))
      (node (ref "R41") (pin "1") (pinfunction "1_1") (pintype "passive"))
    )
    (net (code "12") (name "/BOOT1") (class "Default")
      (node (ref "IC1") (pin "37") (pinfunction "PB2_37") (pintype "passive"))
      (node (ref "R52") (pin "1") (pinfunction "1_1") (pintype "passive"))
    )
    (net (code "13") (name "/Dac1PWM1") (class "Default")
      (node (ref "IC1") (pin "47") (pinfunction "PB10_47") (pintype "passive"))
      (node (ref "R63") (pin "1") (pinfunction "1_1") (pintype "passive"))
    )
    (net (code "14") (name "/Dac1PWM2") (class "Default")
      (node (ref "IC1") (pin "48") (pinfunction "PB11_48") (pintype "passive"))
      (node (ref "R59") (pin "1") (pinfunction "1_1") (pintype "passive"))
    )
    (net (code "15") (name "/Dac2PWM1") (class "Default")
      (node (ref "IC1") (pin "36") (pinfunction "PB1_36") (pintype "passive"))
      (node (ref "R67") (pin "2") (pinfunction "2_2") (pintype "passive"))
    )
    (net (code "16") (name "/Dac2PWM2") (class "Default")
      (node (ref "IC1") (pin "35") (pinfunction "PB0_35") (pintype "passive"))
      (node (ref "R62") (pin "2") (pinfunction "2_2") (pintype "passive"))
    )
    (net (code "17") (name "/DacIn1") (class "Default")
      (node (ref "IC1") (pin "30") (pinfunction "PA5_30") (pintype "passive"))
      (node (ref "R66") (pin "1") (pinfunction "1_1") (pintype "passive"))
    )
    (net (code "18") (name "/DacIn2") (class "Default")
      (node (ref "IC1") (pin "29") (pinfunction "PA4_29") (pintype "passive"))
      (node (ref "R68") (pin "1") (pinfunction "1_1") (pintype "passive"))
    )
    (net (code "19") (name "/DacOut1") (class "Default")
      (node (ref "IC16") (pin "1") (pinfunction "OUT1_1") (pintype "passive"))
      (node (ref "P5") (pin "1") (pinfunction "1_1") (pintype "passive"))
      (node (ref "P5") (pin "2") (pinfunction "2_2") (pintype "passive"))
      (node (ref "R60") (pin "1") (pinfunction "1_1") (pintype "passive"))
    )
    (net (code "20") (name "/DacOut2") (class "Default")
      (node (ref "IC16") (pin "7") (pinfunction "OUT2_7") (pintype "passive"))
      (node (ref "P5") (pin "3") (pinfunction "3_3") (pintype "passive"))
      (node (ref "P5") (pin "4") (pinfunction "4_4") (pintype "passive"))
      (node (ref "R61") (pin "2") (pinfunction "2_2") (pintype "passive"))
    )
    (net (code "21") (name "/DigitalIn1") (class "Default")
      (node (ref "IC1") (pin "58") (pinfunction "PD11_58") (pintype "passive"))
      (node (ref "P3") (pin "1") (pinfunction "1_1") (pintype "passive"))
      (node (ref "R83") (pin "2") (pinfunction "2_2") (pintype "passive"))
    )
    (net (code "22") (name "/DigitalIn2") (class "Default")
      (node (ref "IC1") (pin "57") (pinfunction "PD10_57") (pintype "passive"))
      (node (ref "P3") (pin "2") (pinfunction "2_2") (pintype "passive"))
      (node (ref "R85") (pin "2") (pinfunction "2_2") (pintype "passive"))
    )
    (net (code "23") (name "/DigitalIn3") (class "Default")
      (node (ref "IC1") (pin "56") (pinfunction "PD9_56") (pintype "passive"))
      (node (ref "P3") (pin "3") (pinfunction "3_3") (pintype "passive"))
      (node (ref "R86") (pin "2") (pinfunction "2_2") (pintype "passive"))
    )
    (net (code "24") (name "/DigitalIn4") (class "Default")
      (node (ref "IC1") (pin "55") (pinfunction "PD8_55") (pintype "passive"))
      (node (ref "P3") (pin "4") (pinfunction "4_4") (pintype "passive"))
      (node (ref "R87") (pin "2") (pinfunction "2_2") (pintype "passive"))
    )
    (net (code "25") (name "/ESP_Rx") (class "Default")
      (node (ref "IC1") (pin "68") (pinfunction "PA9_68") (pintype "passive"))
      (node (ref "IC9") (pin "4") (pinfunction "RXD_4") (pintype "passive"))
    )
    (net (code "26") (name "/ESP_Tx") (class "Default")
      (node (ref "IC1") (pin "69") (pinfunction "PA10_69") (pintype "passive"))
      (node (ref "IC9") (pin "5") (pinfunction "TXD_5") (pintype "passive"))
    )
    (net (code "27") (name "/Micro_Reset") (class "Default")
      (node (ref "IC1") (pin "14") (pinfunction "NRST_14") (pintype "passive"))
      (node (ref "R4") (pin "1") (pinfunction "1_1") (pintype "passive"))
      (node (ref "S_PB") (pin "1") (pinfunction "1_1") (pintype "passive"))
    )
    (net (code "28") (name "/RCMeterADC") (class "Default")
      (node (ref "IC1") (pin "15") (pinfunction "PC0_15") (pintype "passive"))
      (node (ref "IC4") (pin "3") (pinfunction "Z_3") (pintype "passive"))
      (node (ref "P1") (pin "1") (pinfunction "1_1") (pintype "passive"))
    )
    (net (code "29") (name "/RCMeterS1") (class "Default")
      (node (ref "IC1") (pin "5") (pinfunction "PE6_5") (pintype "passive"))
      (node (ref "IC4") (pin "11") (pinfunction "S0_11") (pintype "passive"))
    )
    (net (code "30") (name "/RCMeterS2") (class "Default")
      (node (ref "IC1") (pin "7") (pinfunction "PC13-TAMPER-RTC_7") (pintype "passive"))
      (node (ref "IC4") (pin "10") (pinfunction "S1_10") (pintype "passive"))
    )
    (net (code "31") (name "/RCMeterS3") (class "Default")
      (node (ref "IC1") (pin "8") (pinfunction "PC14-OSC32_IN_8") (pintype "passive"))
      (node (ref "IC4") (pin "9") (pinfunction "S2_9") (pintype "passive"))
    )
    (net (code "32") (name "/RCMeterTogglePin") (class "Default")
      (node (ref "IC1") (pin "9") (pinfunction "PC15-OSC32_OUT_9") (pintype "passive"))
      (node (ref "P1") (pin "2") (pinfunction "2_2") (pintype "passive"))
    )
    (net (code "33") (name "/SWCLK") (class "Default")
      (node (ref "IC1") (pin "76") (pinfunction "PA14_76") (pintype "passive"))
      (node (ref "P2") (pin "1") (pinfunction "1_1") (pintype "passive"))
    )
    (net (code "34") (name "/SWDIO") (class "Default")
      (node (ref "IC1") (pin "72") (pinfunction "PA13_72") (pintype "passive"))
      (node (ref "P2") (pin "2") (pinfunction "2_2") (pintype "passive"))
    )
    (net (code "35") (name "/USB_DM") (class "Default")
      (node (ref "IC1") (pin "70") (pinfunction "PA11_70") (pintype "passive"))
      (node (ref "R76") (pin "2") (pinfunction "2_2") (pintype "passive"))
    )
    (net (code "36") (name "/USB_DP") (class "Default")
      (node (ref "IC1") (pin "71") (pinfunction "PA12_71") (pintype "passive"))
      (node (ref "R77") (pin "2") (pinfunction "2_2") (pintype "passive"))
    )
    (net (code "37") (name "/analogOut1PWM1") (class "Default")
      (node (ref "IC1") (pin "95") (pinfunction "PB8_95") (pintype "passive"))
      (node (ref "R71") (pin "1") (pinfunction "1_1") (pintype "passive"))
    )
    (net (code "38") (name "/analogOut1PWM2") (class "Default")
      (node (ref "IC1") (pin "96") (pinfunction "PB9_96") (pintype "passive"))
      (node (ref "R64") (pin "1") (pinfunction "1_1") (pintype "passive"))
    )
    (net (code "39") (name "/analogOut2PWM1") (class "Default")
      (node (ref "IC1") (pin "92") (pinfunction "PB6_92") (pintype "passive"))
      (node (ref "R70") (pin "2") (pinfunction "2_2") (pintype "passive"))
    )
    (net (code "40") (name "/analogOut2PWM2") (class "Default")
      (node (ref "IC1") (pin "93") (pinfunction "PB7_93") (pintype "passive"))
      (node (ref "R73") (pin "2") (pinfunction "2_2") (pintype "passive"))
    )
    (net (code "41") (name "/analogVoltageOut1") (class "Default")
      (node (ref "IC17") (pin "1") (pinfunction "OUT1_1") (pintype "passive"))
      (node (ref "P6") (pin "1") (pinfunction "1_1") (pintype "passive"))
      (node (ref "P6") (pin "2") (pinfunction "2_2") (pintype "passive"))
      (node (ref "R65") (pin "1") (pinfunction "1_1") (pintype "passive"))
    )
    (net (code "42") (name "/analogVoltageOut2") (class "Default")
      (node (ref "IC17") (pin "7") (pinfunction "OUT2_7") (pintype "passive"))
      (node (ref "P6") (pin "3") (pinfunction "3_3") (pintype "passive"))
      (node (ref "P6") (pin "4") (pinfunction "4_4") (pintype "passive"))
      (node (ref "R69") (pin "2") (pinfunction "2_2") (pintype "passive"))
    )
    (net (code "43") (name "/channel1Out1") (class "Default")
      (node (ref "IC15") (pin "12") (pinfunction "0X_12") (pintype "passive"))
      (node (ref "IC2") (pin "7") (pinfunction "OUT2_7") (pintype "passive"))
      (node (ref "R31") (pin "1") (pinfunction "1_1") (pintype "passive"))
    )
    (net (code "44") (name "/channel1Out2") (class "Default")
      (node (ref "IC15") (pin "13") (pinfunction "1X_13") (pintype "passive"))
      (node (ref "IC2") (pin "1") (pinfunction "OUT1_1") (pintype "passive"))
      (node (ref "R2") (pin "1") (pinfunction "1_1") (pintype "passive"))
    )
    (net (code "45") (name "/channel1Select") (class "Default")
      (node (ref "IC1") (pin "2") (pinfunction "PE3_2") (pintype "passive"))
      (node (ref "IC15") (pin "11") (pinfunction "A_11") (pintype "passive"))
    )
    (net (code "46") (name "/channel2Out1") (class "Default")
      (node (ref "IC15") (pin "2") (pinfunction "0Y_2") (pintype "passive"))
      (node (ref "IC6") (pin "7") (pinfunction "OUT2_7") (pintype "passive"))
      (node (ref "R33") (pin "1") (pinfunction "1_1") (pintype "passive"))
    )
    (net (code "47") (name "/channel2Out2") (class "Default")
      (node (ref "IC15") (pin "1") (pinfunction "1Y_1") (pintype "passive"))
      (node (ref "IC6") (pin "1") (pinfunction "OUT1_1") (pintype "passive"))
      (node (ref "R11") (pin "1") (pinfunction "1_1") (pintype "passive"))
    )
    (net (code "48") (name "/channel2Select") (class "Default")
      (node (ref "IC1") (pin "3") (pinfunction "PE4_3") (pintype "passive"))
      (node (ref "IC15") (pin "10") (pinfunction "B_10") (pintype "passive"))
    )
    (net (code "49") (name "/channel3Out1") (class "Default")
      (node (ref "IC13") (pin "7") (pinfunction "OUT2_7") (pintype "passive"))
      (node (ref "IC15") (pin "5") (pinfunction "0Z_5") (pintype "passive"))
      (node (ref "R58") (pin "1") (pinfunction "1_1") (pintype "passive"))
    )
    (net (code "50") (name "/channel3Out2") (class "Default")
      (node (ref "IC13") (pin "1") (pinfunction "OUT1_1") (pintype "passive"))
      (node (ref "IC15") (pin "3") (pinfunction "1Z_3") (pintype "passive"))
      (node (ref "R44") (pin "1") (pinfunction "1_1") (pintype "passive"))
    )
    (net (code "51") (name "/channel3Select") (class "Default")
      (node (ref "IC1") (pin "4") (pinfunction "PE5_4") (pintype "passive"))
      (node (ref "IC15") (pin "9") (pinfunction "C_9") (pintype "passive"))
    )
    (net (code "52") (name "/connectionADC") (class "Default")
      (node (ref "IC1") (pin "17") (pinfunction "PC2_17") (pintype "passive"))
      (node (ref "P12") (pin "1") (pinfunction "1_1") (pintype "passive"))
      (node (ref "R82") (pin "1") (pinfunction "1_1") (pintype "passive"))
    )
    (net (code "53") (name "/currentMeterADC") (class "Default")
      (node (ref "IC1") (pin "16") (pinfunction "PC1_16") (pintype "passive"))
      (node (ref "IC8") (pin "7") (pinfunction "VIOUT_7") (pintype "passive"))
    )
    (net (code "54") (name "/currentMeterIn+") (class "Default")
      (node (ref "IC8") (pin "1") (pinfunction "IP+_1_1") (pintype "passive"))
      (node (ref "IC8") (pin "2") (pinfunction "IP+_2_2") (pintype "passive"))
      (node (ref "J1") (pin "1") (pinfunction "1_1") (pintype "passive"))
    )
    (net (code "55") (name "/currentMeterIn-") (class "Default")
      (node (ref "IC8") (pin "3") (pinfunction "IP-_1_3") (pintype "passive"))
      (node (ref "IC8") (pin "4") (pinfunction "IP-_2_4") (pintype "passive"))
      (node (ref "J1") (pin "2") (pinfunction "2_2") (pintype "passive"))
    )
    (net (code "56") (name "/oscopeADC1") (class "Default")
      (node (ref "IC1") (pin "24") (pinfunction "PA1_24") (pintype "passive"))
      (node (ref "R78") (pin "2") (pinfunction "2_2") (pintype "passive"))
      (node (ref "R88") (pin "2") (pinfunction "2_2") (pintype "passive"))
      (node (ref "R89") (pin "1") (pinfunction "1_1") (pintype "passive"))
    )
    (net (code "57") (name "/oscopeADC1Double") (class "Default")
      (node (ref "IC15") (pin "14") (pinfunction "X-COM_14") (pintype "passive"))
      (node (ref "R88") (pin "1") (pinfunction "1_1") (pintype "passive"))
    )
    (net (code "58") (name "/oscopeADC2") (class "Default")
      (node (ref "IC1") (pin "23") (pinfunction "PA0-WKUP_23") (pintype "passive"))
      (node (ref "R79") (pin "2") (pinfunction "2_2") (pintype "passive"))
      (node (ref "R90") (pin "2") (pinfunction "2_2") (pintype "passive"))
      (node (ref "R91") (pin "1") (pinfunction "1_1") (pintype "passive"))
    )
    (net (code "59") (name "/oscopeADC2Double") (class "Default")
      (node (ref "IC15") (pin "15") (pinfunction "Y-COM_15") (pintype "passive"))
      (node (ref "R90") (pin "1") (pinfunction "1_1") (pintype "passive"))
    )
    (net (code "60") (name "/oscopeADC3") (class "Default")
      (node (ref "IC1") (pin "25") (pinfunction "PA2_25") (pintype "passive"))
      (node (ref "R80") (pin "2") (pinfunction "2_2") (pintype "passive"))
      (node (ref "R92") (pin "2") (pinfunction "2_2") (pintype "passive"))
      (node (ref "R93") (pin "1") (pinfunction "1_1") (pintype "passive"))
    )
    (net (code "61") (name "/oscopeADC3Double") (class "Default")
      (node (ref "IC15") (pin "4") (pinfunction "Z-COM_4") (pintype "passive"))
      (node (ref "R92") (pin "1") (pinfunction "1_1") (pintype "passive"))
    )
    (net (code "62") (name "/oscopeADC4") (class "Default")
      (node (ref "IC1") (pin "26") (pinfunction "PA3_26") (pintype "passive"))
      (node (ref "R81") (pin "2") (pinfunction "2_2") (pintype "passive"))
      (node (ref "R94") (pin "2") (pinfunction "2_2") (pintype "passive"))
      (node (ref "R95") (pin "1") (pinfunction "1_1") (pintype "passive"))
    )
    (net (code "63") (name "/oscopeADC4Double") (class "Default")
      (node (ref "IC11") (pin "1") (pinfunction "OUT1_1") (pintype "passive"))
      (node (ref "R35") (pin "1") (pinfunction "1_1") (pintype "passive"))
      (node (ref "R94") (pin "1") (pinfunction "1_1") (pintype "passive"))
    )
    (net (code "64") (name "/reset_esp") (class "Default")
      (node (ref "IC9") (pin "7") (pinfunction "RST_7") (pintype "passive"))
      (node (ref "R9") (pin "1") (pinfunction "1_1") (pintype "passive"))
      (node (ref "S_esp2") (pin "1") (pinfunction "1_1") (pintype "passive"))
    )
    (net (code "65") (name "GND") (class "Default")
      (node (ref "C1") (pin "1") (pinfunction "1_1") (pintype "passive"))
      (node (ref "C10") (pin "2") (pinfunction "2_2") (pintype "passive"))
      (node (ref "C11") (pin "2") (pinfunction "2_2") (pintype "passive"))
      (node (ref "C12") (pin "2") (pinfunction "2_2") (pintype "passive"))
      (node (ref "C13") (pin "2") (pinfunction "2_2") (pintype "passive"))
      (node (ref "C14") (pin "2") (pinfunction "2_2") (pintype "passive"))
      (node (ref "C15") (pin "2") (pinfunction "2_2") (pintype "passive"))
      (node (ref "C17") (pin "1") (pinfunction "1_1") (pintype "passive"))
      (node (ref "C18") (pin "2") (pinfunction "2_2") (pintype "passive"))
      (node (ref "C2") (pin "1") (pinfunction "1_1") (pintype "passive"))
      (node (ref "C3") (pin "1") (pinfunction "1_1") (pintype "passive"))
      (node (ref "C4") (pin "1") (pinfunction "1_1") (pintype "passive"))
      (node (ref "C5") (pin "1") (pinfunction "1_1") (pintype "passive"))
      (node (ref "C6") (pin "1") (pinfunction "1_1") (pintype "passive"))
      (node (ref "C7") (pin "1") (pinfunction "1_1") (pintype "passive"))
      (node (ref "C8") (pin "2") (pinfunction "2_2") (pintype "passive"))
      (node (ref "D1") (pin "1") (pinfunction "K_1") (pintype "passive"))
      (node (ref "IC1") (pin "10") (pinfunction "VSS_5_10") (pintype "passive"))
      (node (ref "IC1") (pin "19") (pinfunction "VSSA_19") (pintype "passive"))
      (node (ref "IC1") (pin "20") (pinfunction "VREF-_20") (pintype "passive"))
      (node (ref "IC1") (pin "27") (pinfunction "VSS_4_27") (pintype "passive"))
      (node (ref "IC1") (pin "49") (pinfunction "VSS_1_49") (pintype "passive"))
      (node (ref "IC1") (pin "74") (pinfunction "VSS_2_74") (pintype "passive"))
      (node (ref "IC1") (pin "99") (pinfunction "VSS_3_99") (pintype "passive"))
      (node (ref "IC15") (pin "7") (pinfunction "VEE_7") (pintype "passive"))
      (node (ref "IC15") (pin "8") (pinfunction "GND_8") (pintype "passive"))
      (node (ref "IC18") (pin "3") (pinfunction "GND_3") (pintype "passive"))
      (node (ref "IC4") (pin "6") (pinfunction "~{E}_6") (pintype "passive"))
      (node (ref "IC4") (pin "7") (pinfunction "VEE_7") (pintype "passive"))
      (node (ref "IC4") (pin "8") (pinfunction "GND_8") (pintype "passive"))
      (node (ref "IC5") (pin "1") (pinfunction "GND/ADJUST_1") (pintype "passive"))
      (node (ref "IC7") (pin "1") (pinfunction "GND/ADJUST_1") (pintype "passive"))
      (node (ref "IC8") (pin "5") (pinfunction "GND_5") (pintype "passive"))
      (node (ref "IC9") (pin "1") (pinfunction "GND_1") (pintype "passive"))
      (node (ref "J2") (pin "4") (pinfunction "4_4") (pintype "passive"))
      (node (ref "J2") (pin "5") (pinfunction "5_5") (pintype "passive"))
      (node (ref "J2") (pin "MP1") (pinfunction "MP1_MP1") (pintype "passive"))
      (node (ref "J2") (pin "MP2") (pinfunction "MP2_MP2") (pintype "passive"))
      (node (ref "J2") (pin "MP3") (pinfunction "MP3_MP3") (pintype "passive"))
      (node (ref "J2") (pin "MP4") (pinfunction "MP4_MP4") (pintype "passive"))
      (node (ref "J3") (pin "2") (pinfunction "2_2") (pintype "passive"))
      (node (ref "J3") (pin "3") (pinfunction "3_3") (pintype "passive"))
      (node (ref "LEDT1") (pin "2") (pinfunction "K_2") (pintype "passive"))
      (node (ref "LEDT2") (pin "2") (pinfunction "K_2") (pintype "passive"))
      (node (ref "LEDT3") (pin "2") (pinfunction "K_2") (pintype "passive"))
      (node (ref "LEDT4") (pin "2") (pinfunction "K_2") (pintype "passive"))
      (node (ref "LEDT5") (pin "2") (pinfunction "K_2") (pintype "passive"))
      (node (ref "LEDT6") (pin "2") (pinfunction "K_2") (pintype "passive"))
      (node (ref "LEDT7") (pin "2") (pinfunction "K_2") (pintype "passive"))
      (node (ref "LEDT8") (pin "1") (pinfunction "A_1") (pintype "passive"))
      (node (ref "P10") (pin "1") (pinfunction "1_1") (pintype "passive"))
      (node (ref "P10") (pin "2") (pinfunction "2_2") (pintype "passive"))
      (node (ref "P10") (pin "3") (pinfunction "3_3") (pintype "passive"))
      (node (ref "P10") (pin "4") (pinfunction "4_4") (pintype "passive"))
      (node (ref "P11") (pin "1") (pinfunction "1_1") (pintype "passive"))
      (node (ref "P11") (pin "2") (pinfunction "2_2") (pintype "passive"))
      (node (ref "P11") (pin "3") (pinfunction "3_3") (pintype "passive"))
      (node (ref "P11") (pin "4") (pinfunction "4_4") (pintype "passive"))
      (node (ref "P2") (pin "3") (pinfunction "3_3") (pintype "passive"))
      (node (ref "P7") (pin "1") (pinfunction "1_1") (pintype "passive"))
      (node (ref "P7") (pin "2") (pinfunction "2_2") (pintype "passive"))
      (node (ref "P7") (pin "3") (pinfunction "3_3") (pintype "passive"))
      (node (ref "P7") (pin "4") (pinfunction "4_4") (pintype "passive"))
      (node (ref "P8") (pin "4") (pinfunction "4_4") (pintype "passive"))
      (node (ref "P9") (pin "1") (pinfunction "1_1") (pintype "passive"))
      (node (ref "P9") (pin "2") (pinfunction "2_2") (pintype "passive"))
      (node (ref "P9") (pin "3") (pinfunction "3_3") (pintype "passive"))
      (node (ref "P9") (pin "4") (pinfunction "4_4") (pintype "passive"))
      (node (ref "R1") (pin "2") (pinfunction "2_2") (pintype "passive"))
      (node (ref "R10") (pin "2") (pinfunction "2_2") (pintype "passive"))
      (node (ref "R18") (pin "1") (pinfunction "1_1") (pintype "passive"))
      (node (ref "R20") (pin "1") (pinfunction "1_1") (pintype "passive"))
      (node (ref "R27") (pin "1") (pinfunction "1_1") (pintype "passive"))
      (node (ref "R29") (pin "1") (pinfunction "1_1") (pintype "passive"))
      (node (ref "R3") (pin "2") (pinfunction "2_2") (pintype "passive"))
      (node (ref "R30") (pin "2") (pinfunction "2_2") (pintype "passive"))
      (node (ref "R32") (pin "2") (pinfunction "2_2") (pintype "passive"))
      (node (ref "R34") (pin "2") (pinfunction "2_2") (pintype "passive"))
      (node (ref "R43") (pin "2") (pinfunction "2_2") (pintype "passive"))
      (node (ref "R46") (pin "1") (pinfunction "1_1") (pintype "passive"))
      (node (ref "R5") (pin "2") (pinfunction "2_2") (pintype "passive"))
      (node (ref "R50") (pin "1") (pinfunction "1_1") (pintype "passive"))
      (node (ref "R52") (pin "2") (pinfunction "2_2") (pintype "passive"))
      (node (ref "R56") (pin "1") (pinfunction "1_1") (pintype "passive"))
      (node (ref "R57") (pin "2") (pinfunction "2_2") (pintype "passive"))
      (node (ref "R6") (pin "2") (pinfunction "2_2") (pintype "passive"))
      (node (ref "R7") (pin "2") (pinfunction "2_2") (pintype "passive"))
      (node (ref "R72") (pin "1") (pinfunction "1_1") (pintype "passive"))
      (node (ref "R74") (pin "1") (pinfunction "1_1") (pintype "passive"))
      (node (ref "R8") (pin "2") (pinfunction "2_2") (pintype "passive"))
      (node (ref "R83") (pin "1") (pinfunction "1_1") (pintype "passive"))
      (node (ref "R84") (pin "1") (pinfunction "1_1") (pintype "passive"))
      (node (ref "R85") (pin "1") (pinfunction "1_1") (pintype "passive"))
      (node (ref "R86") (pin "1") (pinfunction "1_1") (pintype "passive"))
      (node (ref "R87") (pin "1") (pinfunction "1_1") (pintype "passive"))
      (node (ref "R89") (pin "2") (pinfunction "2_2") (pintype "passive"))
      (node (ref "R91") (pin "2") (pinfunction "2_2") (pintype "passive"))
      (node (ref "R93") (pin "2") (pinfunction "2_2") (pintype "passive"))
      (node (ref "R95") (pin "2") (pinfunction "2_2") (pintype "passive"))
      (node (ref "S_PB") (pin "2") (pinfunction "2_2") (pintype "passive"))
      (node (ref "S_esp2") (pin "2") (pinfunction "2_2") (pintype "passive"))
      (node (ref "Z1") (pin "1") (pinfunction "K_1") (pintype "passive"))
      (node (ref "Z2") (pin "1") (pinfunction "K_1") (pintype "passive"))
      (node (ref "Z3") (pin "1") (pinfunction "K_1") (pintype "passive"))
      (node (ref "Z4") (pin "1") (pinfunction "K_1") (pintype "passive"))
    )
    (net (code "66") (name "Net-(D1-A)") (class "Default")
      (node (ref "D1") (pin "2") (pinfunction "A_2") (pintype "passive"))
      (node (ref "P12") (pin "2") (pinfunction "2_2") (pintype "passive"))
    )
    (net (code "67") (name "Net-(F1-Pad1)") (class "Default")
      (node (ref "F1") (pin "1") (pinfunction "1_1") (pintype "passive"))
      (node (ref "J3") (pin "1") (pinfunction "1_1") (pintype "passive"))
    )
    (net (code "68") (name "Net-(IC1-BOOT0)") (class "Default")
      (node (ref "IC1") (pin "94") (pinfunction "BOOT0_94") (pintype "passive"))
      (node (ref "R3") (pin "1") (pinfunction "1_1") (pintype "passive"))
    )
    (net (code "69") (name "Net-(IC1-OSC_IN)") (class "Default")
      (node (ref "C1") (pin "2") (pinfunction "2_2") (pintype "passive"))
      (node (ref "IC1") (pin "12") (pinfunction "OSC_IN_12") (pintype "passive"))
      (node (ref "crystal1") (pin "1") (pinfunction "1_1") (pintype "passive"))
    )
    (net (code "70") (name "Net-(IC1-OSC_OUT)") (class "Default")
      (node (ref "C4") (pin "2") (pinfunction "2_2") (pintype "passive"))
      (node (ref "IC1") (pin "13") (pinfunction "OSC_OUT_13") (pintype "passive"))
      (node (ref "crystal1") (pin "2") (pinfunction "2_2") (pintype "passive"))
    )
    (net (code "71") (name "Net-(IC1-PC6)") (class "Default")
      (node (ref "IC1") (pin "63") (pinfunction "PC6_63") (pintype "passive"))
      (node (ref "R39") (pin "1") (pinfunction "1_1") (pintype "passive"))
    )
    (net (code "72") (name "Net-(IC1-PC7)") (class "Default")
      (node (ref "IC1") (pin "64") (pinfunction "PC7_64") (pintype "passive"))
      (node (ref "R40") (pin "1") (pinfunction "1_1") (pintype "passive"))
    )
    (net (code "73") (name "Net-(IC1-PD14)") (class "Default")
      (node (ref "IC1") (pin "61") (pinfunction "PD14_61") (pintype "passive"))
      (node (ref "R37") (pin "1") (pinfunction "1_1") (pintype "passive"))
    )
    (net (code "74") (name "Net-(IC1-PD15)") (class "Default")
      (node (ref "IC1") (pin "62") (pinfunction "PD15_62") (pintype "passive"))
      (node (ref "R38") (pin "1") (pinfunction "1_1") (pintype "passive"))
    )
    (net (code "75") (name "Net-(IC2-IN1+)") (class "Default")
      (node (ref "IC2") (pin "3") (pinfunction "IN1+_3") (pintype "passive"))
      (node (ref "R13") (pin "2") (pinfunction "2_2") (pintype "passive"))
      (node (ref "R15") (pin "2") (pinfunction "2_2") (pintype "passive"))
    )
    (net (code "76") (name "Net-(IC2-IN1-)") (class "Default")
      (node (ref "IC2") (pin "2") (pinfunction "IN1-_2") (pintype "passive"))
      (node (ref "R1") (pin "1") (pinfunction "1_1") (pintype "passive"))
      (node (ref "R2") (pin "2") (pinfunction "2_2") (pintype "passive"))
    )
    (net (code "77") (name "Net-(IC2-IN2+)") (class "Default")
      (node (ref "IC2") (pin "5") (pinfunction "IN2+_5") (pintype "passive"))
      (node (ref "R23") (pin "2") (pinfunction "2_2") (pintype "passive"))
      (node (ref "R24") (pin "2") (pinfunction "2_2") (pintype "passive"))
    )
    (net (code "78") (name "Net-(IC2-IN2-)") (class "Default")
      (node (ref "IC2") (pin "6") (pinfunction "IN2-_6") (pintype "passive"))
      (node (ref "R30") (pin "1") (pinfunction "1_1") (pintype "passive"))
      (node (ref "R31") (pin "2") (pinfunction "2_2") (pintype "passive"))
    )
    (net (code "79") (name "Net-(IC3-IN1+)") (class "Default")
      (node (ref "IC3") (pin "3") (pinfunction "IN1+_3") (pintype "passive"))
      (node (ref "R12") (pin "2") (pinfunction "2_2") (pintype "passive"))
      (node (ref "R18") (pin "2") (pinfunction "2_2") (pintype "passive"))
    )
    (net (code "80") (name "Net-(IC3-IN1-)") (class "Default")
      (node (ref "IC3") (pin "1") (pinfunction "OUT1_1") (pintype "passive"))
      (node (ref "IC3") (pin "2") (pinfunction "IN1-_2") (pintype "passive"))
      (node (ref "R13") (pin "1") (pinfunction "1_1") (pintype "passive"))
    )
    (net (code "81") (name "Net-(IC3-IN2+)") (class "Default")
      (node (ref "IC3") (pin "5") (pinfunction "IN2+_5") (pintype "passive"))
      (node (ref "R22") (pin "2") (pinfunction "2_2") (pintype "passive"))
      (node (ref "R27") (pin "2") (pinfunction "2_2") (pintype "passive"))
    )
    (net (code "82") (name "Net-(IC3-IN2-)") (class "Default")
      (node (ref "IC3") (pin "6") (pinfunction "IN2-_6") (pintype "passive"))
      (node (ref "IC3") (pin "7") (pinfunction "OUT2_7") (pintype "passive"))
      (node (ref "R23") (pin "1") (pinfunction "1_1") (pintype "passive"))
    )
    (net (code "83") (name "Net-(IC4-Y0)") (class "Default")
      (node (ref "IC4") (pin "13") (pinfunction "Y0_13") (pintype "passive"))
      (node (ref "R7") (pin "1") (pinfunction "1_1") (pintype "passive"))
    )
    (net (code "84") (name "Net-(IC4-Y1)") (class "Default")
      (node (ref "IC4") (pin "14") (pinfunction "Y1_14") (pintype "passive"))
      (node (ref "R6") (pin "1") (pinfunction "1_1") (pintype "passive"))
    )
    (net (code "85") (name "Net-(IC4-Y2)") (class "Default")
      (node (ref "IC4") (pin "15") (pinfunction "Y2_15") (pintype "passive"))
      (node (ref "R5") (pin "1") (pinfunction "1_1") (pintype "passive"))
    )
    (net (code "86") (name "Net-(IC4-Y3)") (class "Default")
      (node (ref "IC4") (pin "12") (pinfunction "Y3_12") (pintype "passive"))
      (node (ref "R8") (pin "1") (pinfunction "1_1") (pintype "passive"))
    )
    (net (code "87") (name "Net-(IC4-Y4)") (class "Default")
      (node (ref "IC4") (pin "1") (pinfunction "Y4_1") (pintype "passive"))
      (node (ref "R84") (pin "2") (pinfunction "2_2") (pintype "passive"))
    )
    (net (code "88") (name "Net-(IC4-Y5)") (class "Default")
      (node (ref "C7") (pin "2") (pinfunction "2_2") (pintype "passive"))
      (node (ref "IC4") (pin "5") (pinfunction "Y5_5") (pintype "passive"))
    )
    (net (code "89") (name "Net-(IC4-Y6)") (class "Default")
      (node (ref "C5") (pin "2") (pinfunction "2_2") (pintype "passive"))
      (node (ref "IC4") (pin "2") (pinfunction "Y6_2") (pintype "passive"))
    )
    (net (code "90") (name "Net-(IC4-Y7)") (class "Default")
      (node (ref "C6") (pin "2") (pinfunction "2_2") (pintype "passive"))
      (node (ref "IC4") (pin "4") (pinfunction "Y7_4") (pintype "passive"))
    )
    (net (code "91") (name "Net-(IC6-IN1+)") (class "Default")
      (node (ref "IC6") (pin "3") (pinfunction "IN1+_3") (pintype "passive"))
      (node (ref "R17") (pin "2") (pinfunction "2_2") (pintype "passive"))
      (node (ref "R19") (pin "2") (pinfunction "2_2") (pintype "passive"))
    )
    (net (code "92") (name "Net-(IC6-IN1-)") (class "Default")
      (node (ref "IC6") (pin "2") (pinfunction "IN1-_2") (pintype "passive"))
      (node (ref "R10") (pin "1") (pinfunction "1_1") (pintype "passive"))
      (node (ref "R11") (pin "2") (pinfunction "2_2") (pintype "passive"))
    )
    (net (code "93") (name "Net-(IC6-IN2+)") (class "Default")
      (node (ref "IC6") (pin "5") (pinfunction "IN2+_5") (pintype "passive"))
      (node (ref "R26") (pin "2") (pinfunction "2_2") (pintype "passive"))
      (node (ref "R28") (pin "2") (pinfunction "2_2") (pintype "passive"))
    )
    (net (code "94") (name "Net-(IC6-IN2-)") (class "Default")
      (node (ref "IC6") (pin "6") (pinfunction "IN2-_6") (pintype "passive"))
      (node (ref "R32") (pin "1") (pinfunction "1_1") (pintype "passive"))
      (node (ref "R33") (pin "2") (pinfunction "2_2") (pintype "passive"))
    )
    (net (code "95") (name "Net-(IC8-FILTER)") (class "Default")
      (node (ref "C2") (pin "2") (pinfunction "2_2") (pintype "passive"))
      (node (ref "IC8") (pin "6") (pinfunction "FILTER_6") (pintype "passive"))
    )
    (net (code "96") (name "Net-(IC10-IN1+)") (class "Default")
      (node (ref "IC10") (pin "3") (pinfunction "IN1+_3") (pintype "passive"))
      (node (ref "R16") (pin "2") (pinfunction "2_2") (pintype "passive"))
      (node (ref "R20") (pin "2") (pinfunction "2_2") (pintype "passive"))
    )
    (net (code "97") (name "Net-(IC10-IN1-)") (class "Default")
      (node (ref "IC10") (pin "1") (pinfunction "OUT1_1") (pintype "passive"))
      (node (ref "IC10") (pin "2") (pinfunction "IN1-_2") (pintype "passive"))
      (node (ref "R17") (pin "1") (pinfunction "1_1") (pintype "passive"))
    )
    (net (code "98") (name "Net-(IC10-IN2+)") (class "Default")
      (node (ref "IC10") (pin "5") (pinfunction "IN2+_5") (pintype "passive"))
      (node (ref "R25") (pin "2") (pinfunction "2_2") (pintype "passive"))
      (node (ref "R29") (pin "2") (pinfunction "2_2") (pintype "passive"))
    )
    (net (code "99") (name "Net-(IC10-IN2-)") (class "Default")
      (node (ref "IC10") (pin "6") (pinfunction "IN2-_6") (pintype "passive"))
      (node (ref "IC10") (pin "7") (pinfunction "OUT2_7") (pintype "passive"))
      (node (ref "R26") (pin "1") (pinfunction "1_1") (pintype "passive"))
    )
    (net (code "100") (name "Net-(IC11-IN1+)") (class "Default")
      (node (ref "IC11") (pin "3") (pinfunction "IN1+_3") (pintype "passive"))
      (node (ref "R42") (pin "2") (pinfunction "2_2") (pintype "passive"))
      (node (ref "R45") (pin "2") (pinfunction "2_2") (pintype "passive"))
    )
    (net (code "101") (name "Net-(IC11-IN1-)") (class "Default")
      (node (ref "IC11") (pin "2") (pinfunction "IN1-_2") (pintype "passive"))
      (node (ref "R34") (pin "1") (pinfunction "1_1") (pintype "passive"))
      (node (ref "R35") (pin "2") (pinfunction "2_2") (pintype "passive"))
    )
    (net (code "102") (name "Net-(IC12-IN1+)") (class "Default")
      (node (ref "IC12") (pin "3") (pinfunction "IN1+_3") (pintype "passive"))
      (node (ref "R41") (pin "2") (pinfunction "2_2") (pintype "passive"))
      (node (ref "R46") (pin "2") (pinfunction "2_2") (pintype "passive"))
    )
    (net (code "103") (name "Net-(IC12-IN1-)") (class "Default")
      (node (ref "IC12") (pin "1") (pinfunction "OUT1_1") (pintype "passive"))
      (node (ref "IC12") (pin "2") (pinfunction "IN1-_2") (pintype "passive"))
      (node (ref "R42") (pin "1") (pinfunction "1_1") (pintype "passive"))
    )
    (net (code "104") (name "Net-(IC13-IN1+)") (class "Default")
      (node (ref "IC13") (pin "3") (pinfunction "IN1+_3") (pintype "passive"))
      (node (ref "R48") (pin "2") (pinfunction "2_2") (pintype "passive"))
      (node (ref "R49") (pin "2") (pinfunction "2_2") (pintype "passive"))
    )
    (net (code "105") (name "Net-(IC13-IN1-)") (class "Default")
      (node (ref "IC13") (pin "2") (pinfunction "IN1-_2") (pintype "passive"))
      (node (ref "R43") (pin "1") (pinfunction "1_1") (pintype "passive"))
      (node (ref "R44") (pin "2") (pinfunction "2_2") (pintype "passive"))
    )
    (net (code "106") (name "Net-(IC13-IN2+)") (class "Default")
      (node (ref "IC13") (pin "5") (pinfunction "IN2+_5") (pintype "passive"))
      (node (ref "R54") (pin "2") (pinfunction "2_2") (pintype "passive"))
      (node (ref "R55") (pin "2") (pinfunction "2_2") (pintype "passive"))
    )
    (net (code "107") (name "Net-(IC13-IN2-)") (class "Default")
      (node (ref "IC13") (pin "6") (pinfunction "IN2-_6") (pintype "passive"))
      (node (ref "R57") (pin "1") (pinfunction "1_1") (pintype "passive"))
      (node (ref "R58") (pin "2") (pinfunction "2_2") (pintype "passive"))
    )
    (net (code "108") (name "Net-(IC14-IN1+)") (class "Default")
      (node (ref "IC14") (pin "3") (pinfunction "IN1+_3") (pintype "passive"))
      (node (ref "R47") (pin "2") (pinfunction "2_2") (pintype "passive"))
      (node (ref "R50") (pin "2") (pinfunction "2_2") (pintype "passive"))
    )
    (net (code "109") (name "Net-(IC14-IN1-)") (class "Default")
      (node (ref "IC14") (pin "1") (pinfunction "OUT1_1") (pintype "passive"))
      (node (ref "IC14") (pin "2") (pinfunction "IN1-_2") (pintype "passive"))
      (node (ref "R48") (pin "1") (pinfunction "1_1") (pintype "passive"))
    )
    (net (code "110") (name "Net-(IC14-IN2+)") (class "Default")
      (node (ref "IC14") (pin "5") (pinfunction "IN2+_5") (pintype "passive"))
      (node (ref "R53") (pin "2") (pinfunction "2_2") (pintype "passive"))
      (node (ref "R56") (pin "2") (pinfunction "2_2") (pintype "passive"))
    )
    (net (code "111") (name "Net-(IC14-IN2-)") (class "Default")
      (node (ref "IC14") (pin "6") (pinfunction "IN2-_6") (pintype "passive"))
      (node (ref "IC14") (pin "7") (pinfunction "OUT2_7") (pintype "passive"))
      (node (ref "R54") (pin "1") (pinfunction "1_1") (pintype "passive"))
    )
    (net (code "112") (name "Net-(IC16-IN1+)") (class "Default")
      (node (ref "IC16") (pin "3") (pinfunction "IN1+_3") (pintype "passive"))
      (node (ref "R63") (pin "2") (pinfunction "2_2") (pintype "passive"))
      (node (ref "R66") (pin "2") (pinfunction "2_2") (pintype "passive"))
    )
    (net (code "113") (name "Net-(IC16-IN1-)") (class "Default")
      (node (ref "IC16") (pin "2") (pinfunction "IN1-_2") (pintype "passive"))
      (node (ref "R59") (pin "2") (pinfunction "2_2") (pintype "passive"))
      (node (ref "R60") (pin "2") (pinfunction "2_2") (pintype "passive"))
    )
    (net (code "114") (name "Net-(IC16-IN2+)") (class "Default")
      (node (ref "IC16") (pin "5") (pinfunction "IN2+_5") (pintype "passive"))
      (node (ref "R67") (pin "1") (pinfunction "1_1") (pintype "passive"))
      (node (ref "R68") (pin "2") (pinfunction "2_2") (pintype "passive"))
    )
    (net (code "115") (name "Net-(IC16-IN2-)") (class "Default")
      (node (ref "IC16") (pin "6") (pinfunction "IN2-_6") (pintype "passive"))
      (node (ref "R61") (pin "1") (pinfunction "1_1") (pintype "passive"))
      (node (ref "R62") (pin "1") (pinfunction "1_1") (pintype "passive"))
    )
    (net (code "116") (name "Net-(IC17-IN1+)") (class "Default")
      (node (ref "IC17") (pin "3") (pinfunction "IN1+_3") (pintype "passive"))
      (node (ref "R71") (pin "2") (pinfunction "2_2") (pintype "passive"))
      (node (ref "R72") (pin "2") (pinfunction "2_2") (pintype "passive"))
    )
    (net (code "117") (name "Net-(IC17-IN1-)") (class "Default")
      (node (ref "IC17") (pin "2") (pinfunction "IN1-_2") (pintype "passive"))
      (node (ref "R64") (pin "2") (pinfunction "2_2") (pintype "passive"))
      (node (ref "R65") (pin "2") (pinfunction "2_2") (pintype "passive"))
    )
    (net (code "118") (name "Net-(IC17-IN2+)") (class "Default")
      (node (ref "IC17") (pin "5") (pinfunction "IN2+_5") (pintype "passive"))
      (node (ref "R73") (pin "1") (pinfunction "1_1") (pintype "passive"))
      (node (ref "R74") (pin "2") (pinfunction "2_2") (pintype "passive"))
    )
    (net (code "119") (name "Net-(IC17-IN2-)") (class "Default")
      (node (ref "IC17") (pin "6") (pinfunction "IN2-_6") (pintype "passive"))
      (node (ref "R69") (pin "1") (pinfunction "1_1") (pintype "passive"))
      (node (ref "R70") (pin "1") (pinfunction "1_1") (pintype "passive"))
    )
    (net (code "120") (name "Net-(IC18-CAP+)") (class "Default")
      (node (ref "C16") (pin "2") (pinfunction "2_2") (pintype "passive"))
      (node (ref "IC18") (pin "2") (pinfunction "CAP+_2") (pintype "passive"))
    )
    (net (code "121") (name "Net-(IC18-CAP-)") (class "Default")
      (node (ref "C16") (pin "1") (pinfunction "1_1") (pintype "passive"))
      (node (ref "IC18") (pin "4") (pinfunction "CAP-_4") (pintype "passive"))
    )
    (net (code "122") (name "Net-(J2-Pad2)") (class "Default")
      (node (ref "J2") (pin "2") (pinfunction "2_2") (pintype "passive"))
      (node (ref "R76") (pin "1") (pinfunction "1_1") (pintype "passive"))
    )
    (net (code "123") (name "Net-(J2-Pad3)") (class "Default")
      (node (ref "J2") (pin "3") (pinfunction "3_3") (pintype "passive"))
      (node (ref "R75") (pin "1") (pinfunction "1_1") (pintype "passive"))
      (node (ref "R77") (pin "1") (pinfunction "1_1") (pintype "passive"))
    )
    (net (code "124") (name "Net-(LEDT1-A)") (class "Default")
      (node (ref "LEDT1") (pin "1") (pinfunction "A_1") (pintype "passive"))
      (node (ref "R14") (pin "2") (pinfunction "2_2") (pintype "passive"))
    )
    (net (code "125") (name "Net-(LEDT2-A)") (class "Default")
      (node (ref "LEDT2") (pin "1") (pinfunction "A_1") (pintype "passive"))
      (node (ref "R21") (pin "2") (pinfunction "2_2") (pintype "passive"))
    )
    (net (code "126") (name "Net-(LEDT3-A)") (class "Default")
      (node (ref "LEDT3") (pin "1") (pinfunction "A_1") (pintype "passive"))
      (node (ref "R36") (pin "2") (pinfunction "2_2") (pintype "passive"))
    )
    (net (code "127") (name "Net-(LEDT4-A)") (class "Default")
      (node (ref "LEDT4") (pin "1") (pinfunction "A_1") (pintype "passive"))
      (node (ref "R37") (pin "2") (pinfunction "2_2") (pintype "passive"))
    )
    (net (code "128") (name "Net-(LEDT5-A)") (class "Default")
      (node (ref "LEDT5") (pin "1") (pinfunction "A_1") (pintype "passive"))
      (node (ref "R38") (pin "2") (pinfunction "2_2") (pintype "passive"))
    )
    (net (code "129") (name "Net-(LEDT6-A)") (class "Default")
      (node (ref "LEDT6") (pin "1") (pinfunction "A_1") (pintype "passive"))
      (node (ref "R39") (pin "2") (pinfunction "2_2") (pintype "passive"))
    )
    (net (code "130") (name "Net-(LEDT7-A)") (class "Default")
      (node (ref "LEDT7") (pin "1") (pinfunction "A_1") (pintype "passive"))
      (node (ref "R40") (pin "2") (pinfunction "2_2") (pintype "passive"))
    )
    (net (code "131") (name "Net-(LEDT8-K)") (class "Default")
      (node (ref "LEDT8") (pin "2") (pinfunction "K_2") (pintype "passive"))
      (node (ref "R51") (pin "2") (pinfunction "2_2") (pintype "passive"))
    )
    (net (code "132") (name "Net-(Z1-A)") (class "Default")
      (node (ref "R78") (pin "1") (pinfunction "1_1") (pintype "passive"))
      (node (ref "Z1") (pin "2") (pinfunction "A_2") (pintype "passive"))
    )
    (net (code "133") (name "Net-(Z2-A)") (class "Default")
      (node (ref "R79") (pin "1") (pinfunction "1_1") (pintype "passive"))
      (node (ref "Z2") (pin "2") (pinfunction "A_2") (pintype "passive"))
    )
    (net (code "134") (name "Net-(Z3-A)") (class "Default")
      (node (ref "R80") (pin "1") (pinfunction "1_1") (pintype "passive"))
      (node (ref "Z3") (pin "2") (pinfunction "A_2") (pintype "passive"))
    )
    (net (code "135") (name "Net-(Z4-A)") (class "Default")
      (node (ref "R81") (pin "1") (pinfunction "1_1") (pintype "passive"))
      (node (ref "Z4") (pin "2") (pinfunction "A_2") (pintype "passive"))
    )
    (net (code "136") (name "USB_on") (class "Default")
      (node (ref "IC1") (pin "77") (pinfunction "PA15_77") (pintype "passive"))
      (node (ref "R75") (pin "2") (pinfunction "2_2") (pintype "passive"))
    )
    (net (code "137") (name "unconnected-(IC1-NC-Pad73)") (class "Default")
      (node (ref "IC1") (pin "73") (pinfunction "NC_73") (pintype "passive"))
    )
    (net (code "138") (name "unconnected-(IC1-PA6-Pad31)") (class "Default")
      (node (ref "IC1") (pin "31") (pinfunction "PA6_31") (pintype "passive"))
    )
    (net (code "139") (name "unconnected-(IC1-PA7-Pad32)") (class "Default")
      (node (ref "IC1") (pin "32") (pinfunction "PA7_32") (pintype "passive"))
    )
    (net (code "140") (name "unconnected-(IC1-PA8-Pad67)") (class "Default")
      (node (ref "IC1") (pin "67") (pinfunction "PA8_67") (pintype "passive"))
    )
    (net (code "141") (name "unconnected-(IC1-PB3-Pad89)") (class "Default")
      (node (ref "IC1") (pin "89") (pinfunction "PB3_89") (pintype "passive"))
    )
    (net (code "142") (name "unconnected-(IC1-PB4-Pad90)") (class "Default")
      (node (ref "IC1") (pin "90") (pinfunction "PB4_90") (pintype "passive"))
    )
    (net (code "143") (name "unconnected-(IC1-PB5-Pad91)") (class "Default")
      (node (ref "IC1") (pin "91") (pinfunction "PB5_91") (pintype "passive"))
    )
    (net (code "144") (name "unconnected-(IC1-PB12-Pad51)") (class "Default")
      (node (ref "IC1") (pin "51") (pinfunction "PB12_51") (pintype "passive"))
    )
    (net (code "145") (name "unconnected-(IC1-PB13-Pad52)") (class "Default")
      (node (ref "IC1") (pin "52") (pinfunction "PB13_52") (pintype "passive"))
    )
    (net (code "146") (name "unconnected-(IC1-PB14-Pad53)") (class "Default")
      (node (ref "IC1") (pin "53") (pinfunction "PB14_53") (pintype "passive"))
    )
    (net (code "147") (name "unconnected-(IC1-PB15-Pad54)") (class "Default")
      (node (ref "IC1") (pin "54") (pinfunction "PB15_54") (pintype "passive"))
    )
    (net (code "148") (name "unconnected-(IC1-PC3-Pad18)") (class "Default")
      (node (ref "IC1") (pin "18") (pinfunction "PC3_18") (pintype "passive"))
    )
    (net (code "149") (name "unconnected-(IC1-PC4-Pad33)") (class "Default")
      (node (ref "IC1") (pin "33") (pinfunction "PC4_33") (pintype "passive"))
    )
    (net (code "150") (name "unconnected-(IC1-PC5-Pad34)") (class "Default")
      (node (ref "IC1") (pin "34") (pinfunction "PC5_34") (pintype "passive"))
    )
    (net (code "151") (name "unconnected-(IC1-PC8-Pad65)") (class "Default")
      (node (ref "IC1") (pin "65") (pinfunction "PC8_65") (pintype "passive"))
    )
    (net (code "152") (name "unconnected-(IC1-PC9-Pad66)") (class "Default")
      (node (ref "IC1") (pin "66") (pinfunction "PC9_66") (pintype "passive"))
    )
    (net (code "153") (name "unconnected-(IC1-PC10-Pad78)") (class "Default")
      (node (ref "IC1") (pin "78") (pinfunction "PC10_78") (pintype "passive"))
    )
    (net (code "154") (name "unconnected-(IC1-PC11-Pad79)") (class "Default")
      (node (ref "IC1") (pin "79") (pinfunction "PC11_79") (pintype "passive"))
    )
    (net (code "155") (name "unconnected-(IC1-PC12-Pad80)") (class "Default")
      (node (ref "IC1") (pin "80") (pinfunction "PC12_80") (pintype "passive"))
    )
    (net (code "156") (name "unconnected-(IC1-PD0-Pad81)") (class "Default")
      (node (ref "IC1") (pin "81") (pinfunction "PD0_81") (pintype "passive"))
    )
    (net (code "157") (name "unconnected-(IC1-PD1-Pad82)") (class "Default")
      (node (ref "IC1") (pin "82") (pinfunction "PD1_82") (pintype "passive"))
    )
    (net (code "158") (name "unconnected-(IC1-PD2-Pad83)") (class "Default")
      (node (ref "IC1") (pin "83") (pinfunction "PD2_83") (pintype "passive"))
    )
    (net (code "159") (name "unconnected-(IC1-PD3-Pad84)") (class "Default")
      (node (ref "IC1") (pin "84") (pinfunction "PD3_84") (pintype "passive"))
    )
    (net (code "160") (name "unconnected-(IC1-PD4-Pad85)") (class "Default")
      (node (ref "IC1") (pin "85") (pinfunction "PD4_85") (pintype "passive"))
    )
    (net (code "161") (name "unconnected-(IC1-PD5-Pad86)") (class "Default")
      (node (ref "IC1") (pin "86") (pinfunction "PD5_86") (pintype "passive"))
    )
    (net (code "162") (name "unconnected-(IC1-PD6-Pad87)") (class "Default")
      (node (ref "IC1") (pin "87") (pinfunction "PD6_87") (pintype "passive"))
    )
    (net (code "163") (name "unconnected-(IC1-PD7-Pad88)") (class "Default")
      (node (ref "IC1") (pin "88") (pinfunction "PD7_88") (pintype "passive"))
    )
    (net (code "164") (name "unconnected-(IC1-PD12-Pad59)") (class "Default")
      (node (ref "IC1") (pin "59") (pinfunction "PD12_59") (pintype "passive"))
    )
    (net (code "165") (name "unconnected-(IC1-PD13-Pad60)") (class "Default")
      (node (ref "IC1") (pin "60") (pinfunction "PD13_60") (pintype "passive"))
    )
    (net (code "166") (name "unconnected-(IC1-PE0-Pad97)") (class "Default")
      (node (ref "IC1") (pin "97") (pinfunction "PE0_97") (pintype "passive"))
    )
    (net (code "167") (name "unconnected-(IC1-PE1-Pad98)") (class "Default")
      (node (ref "IC1") (pin "98") (pinfunction "PE1_98") (pintype "passive"))
    )
    (net (code "168") (name "unconnected-(IC1-PE2-Pad1)") (class "Default")
      (node (ref "IC1") (pin "1") (pinfunction "PE2_1") (pintype "passive"))
    )
    (net (code "169") (name "unconnected-(IC1-PE7-Pad38)") (class "Default")
      (node (ref "IC1") (pin "38") (pinfunction "PE7_38") (pintype "passive"))
    )
    (net (code "170") (name "unconnected-(IC1-PE8-Pad39)") (class "Default")
      (node (ref "IC1") (pin "39") (pinfunction "PE8_39") (pintype "passive"))
    )
    (net (code "171") (name "unconnected-(IC1-PE9-Pad40)") (class "Default")
      (node (ref "IC1") (pin "40") (pinfunction "PE9_40") (pintype "passive"))
    )
    (net (code "172") (name "unconnected-(IC1-PE10-Pad41)") (class "Default")
      (node (ref "IC1") (pin "41") (pinfunction "PE10_41") (pintype "passive"))
    )
    (net (code "173") (name "unconnected-(IC1-PE11-Pad42)") (class "Default")
      (node (ref "IC1") (pin "42") (pinfunction "PE11_42") (pintype "passive"))
    )
    (net (code "174") (name "unconnected-(IC1-PE12-Pad43)") (class "Default")
      (node (ref "IC1") (pin "43") (pinfunction "PE12_43") (pintype "passive"))
    )
    (net (code "175") (name "unconnected-(IC1-PE13-Pad44)") (class "Default")
      (node (ref "IC1") (pin "44") (pinfunction "PE13_44") (pintype "passive"))
    )
    (net (code "176") (name "unconnected-(IC1-PE14-Pad45)") (class "Default")
      (node (ref "IC1") (pin "45") (pinfunction "PE14_45") (pintype "passive"))
    )
    (net (code "177") (name "unconnected-(IC1-PE15-Pad46)") (class "Default")
      (node (ref "IC1") (pin "46") (pinfunction "PE15_46") (pintype "passive"))
    )
    (net (code "178") (name "unconnected-(IC11-IN2+-Pad5)") (class "Default")
      (node (ref "IC11") (pin "5") (pinfunction "IN2+_5") (pintype "passive"))
    )
    (net (code "179") (name "unconnected-(IC11-IN2--Pad6)") (class "Default")
      (node (ref "IC11") (pin "6") (pinfunction "IN2-_6") (pintype "passive"))
    )
    (net (code "180") (name "unconnected-(IC11-OUT2-Pad7)") (class "Default")
      (node (ref "IC11") (pin "7") (pinfunction "OUT2_7") (pintype "passive"))
    )
    (net (code "181") (name "unconnected-(IC12-IN2+-Pad5)") (class "Default")
      (node (ref "IC12") (pin "5") (pinfunction "IN2+_5") (pintype "passive"))
    )
    (net (code "182") (name "unconnected-(IC12-IN2--Pad6)") (class "Default")
      (node (ref "IC12") (pin "6") (pinfunction "IN2-_6") (pintype "passive"))
    )
    (net (code "183") (name "unconnected-(IC12-OUT2-Pad7)") (class "Default")
      (node (ref "IC12") (pin "7") (pinfunction "OUT2_7") (pintype "passive"))
    )
    (net (code "184") (name "unconnected-(IC15-INH-Pad6)") (class "Default")
      (node (ref "IC15") (pin "6") (pinfunction "INH_6") (pintype "passive"))
    )
    (net (code "185") (name "unconnected-(IC18-LV-Pad6)") (class "Default")
      (node (ref "IC18") (pin "6") (pinfunction "LV_6") (pintype "passive"))
    )
    (net (code "186") (name "unconnected-(IC18-NC-Pad1)") (class "Default")
      (node (ref "IC18") (pin "1") (pinfunction "NC_1") (pintype "passive"))
    )
    (net (code "187") (name "unconnected-(IC18-OSC-Pad7)") (class "Default")
      (node (ref "IC18") (pin "7") (pinfunction "OSC_7") (pintype "passive"))
    )
    (net (code "188") (name "unconnected-(J2-Pad1)") (class "Default")
      (node (ref "J2") (pin "1") (pinfunction "1_1") (pintype "passive"))
    )
  )
)
